# interfacez_main_r2_3.net
KiCad netlist of a schematic drawn in EAGLE
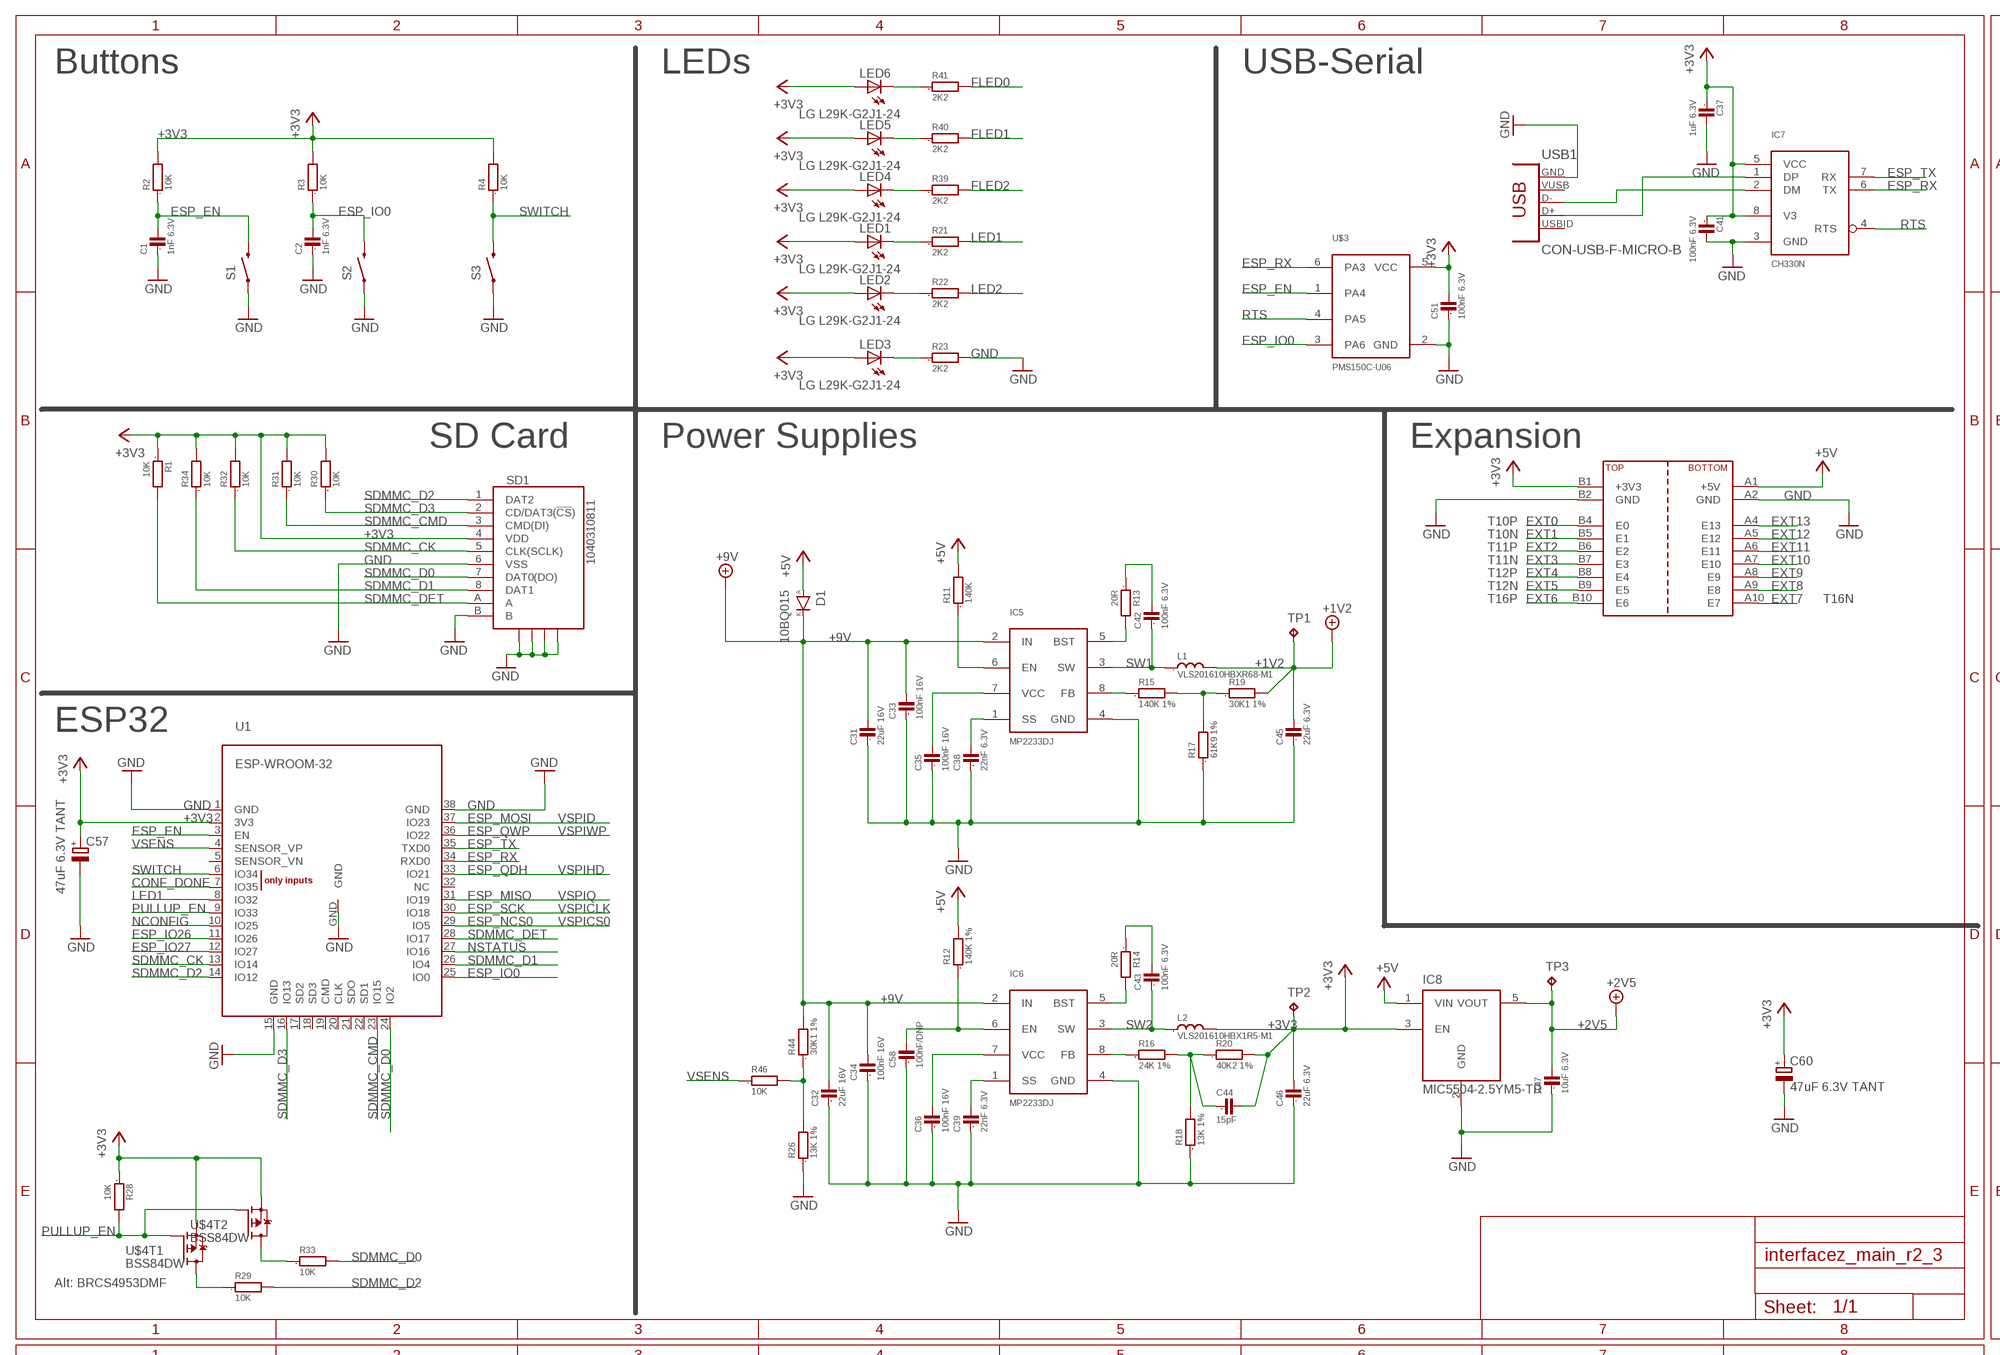
[diagram p0: schematic, sheet 1, part 1 of 3]
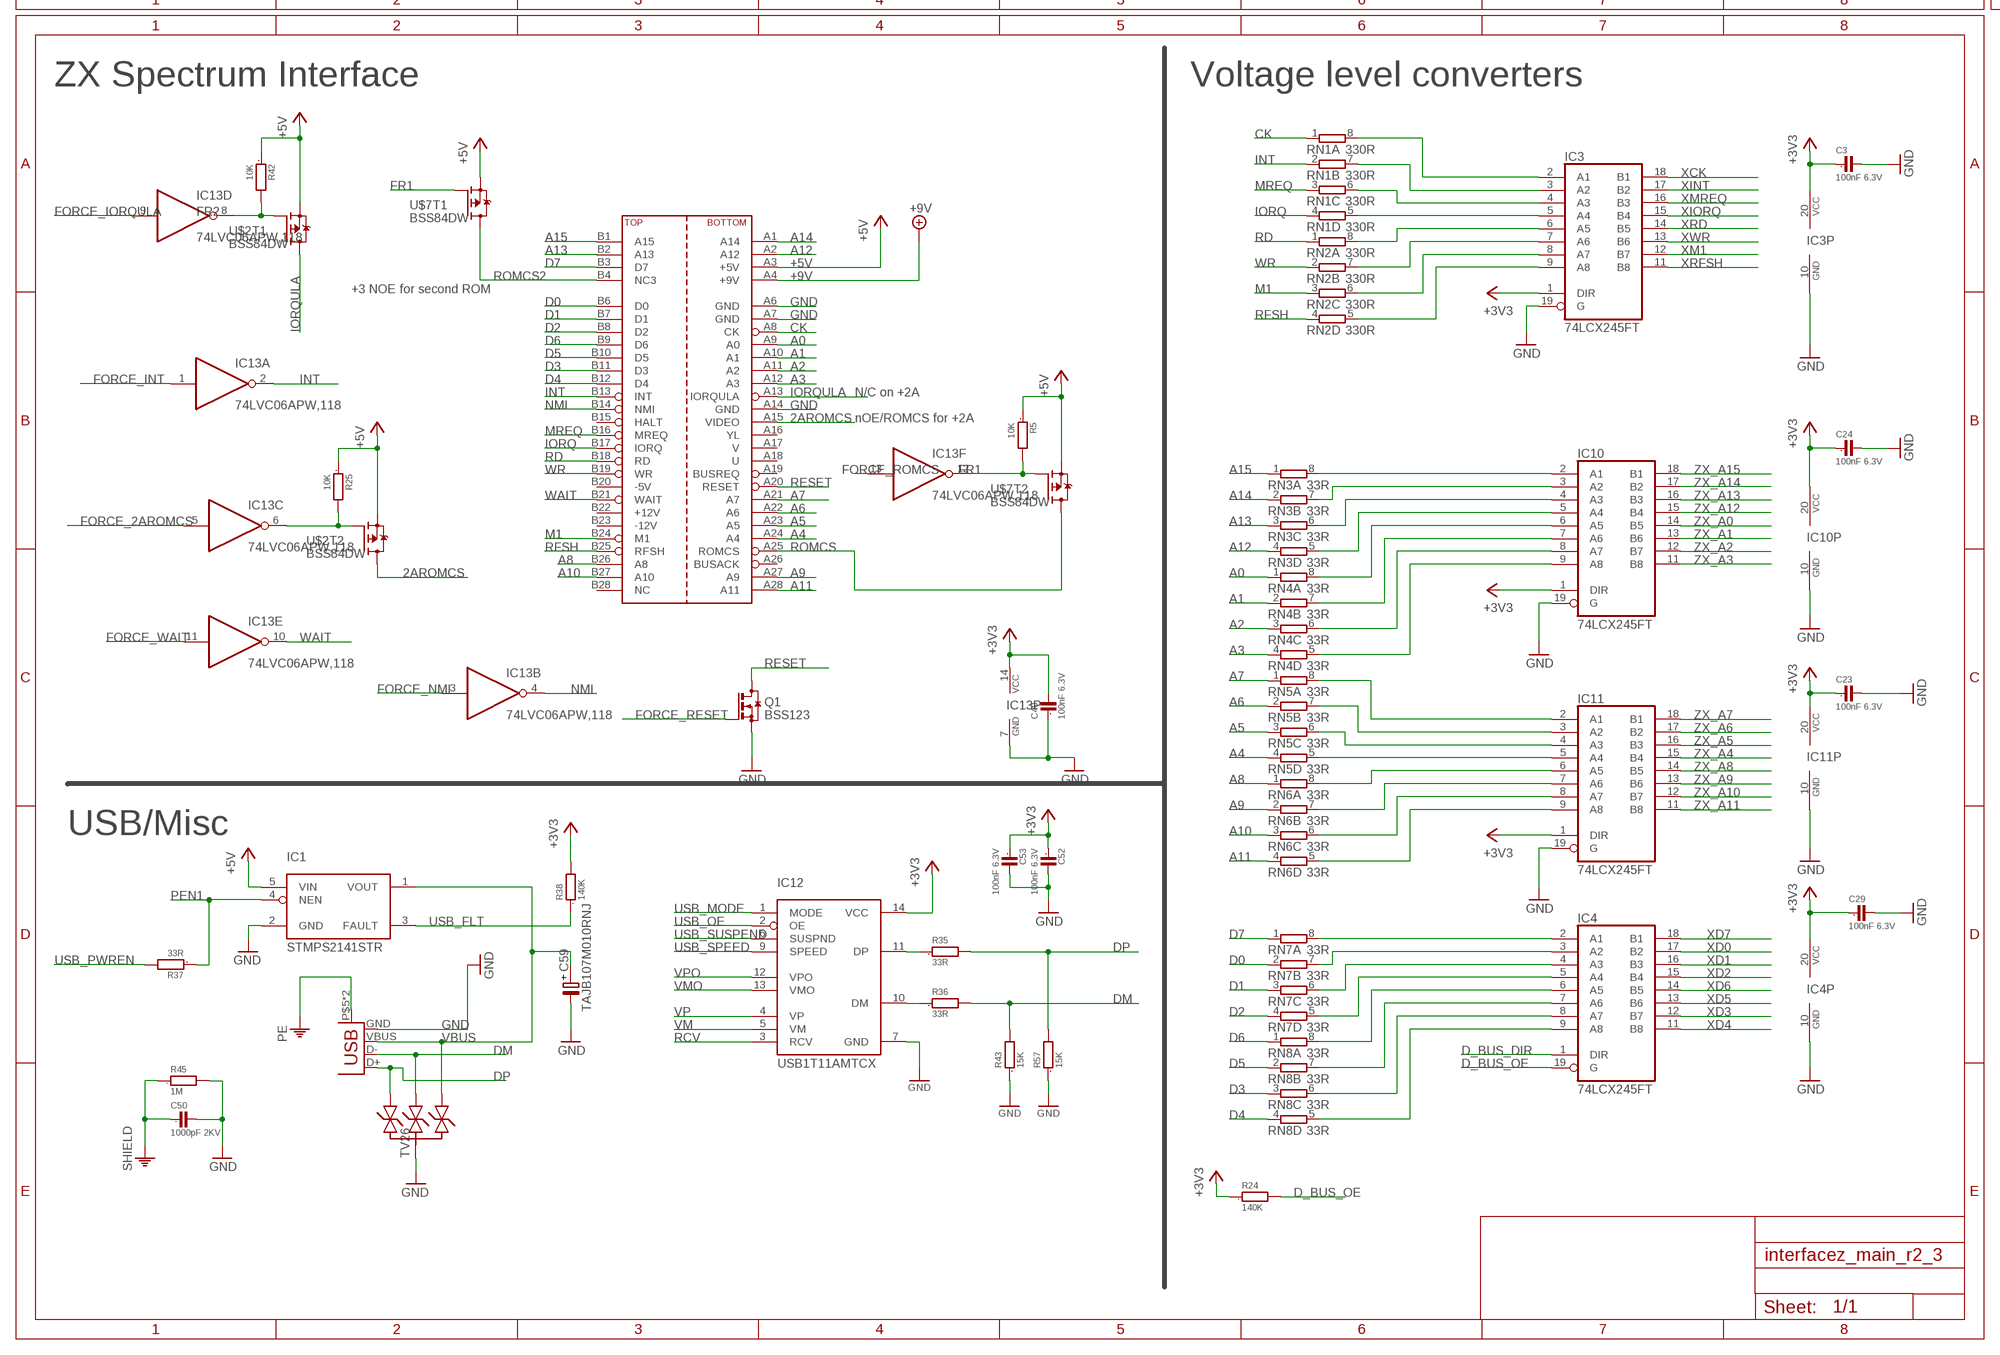
[diagram p1: schematic, sheet 1, part 2 of 3]
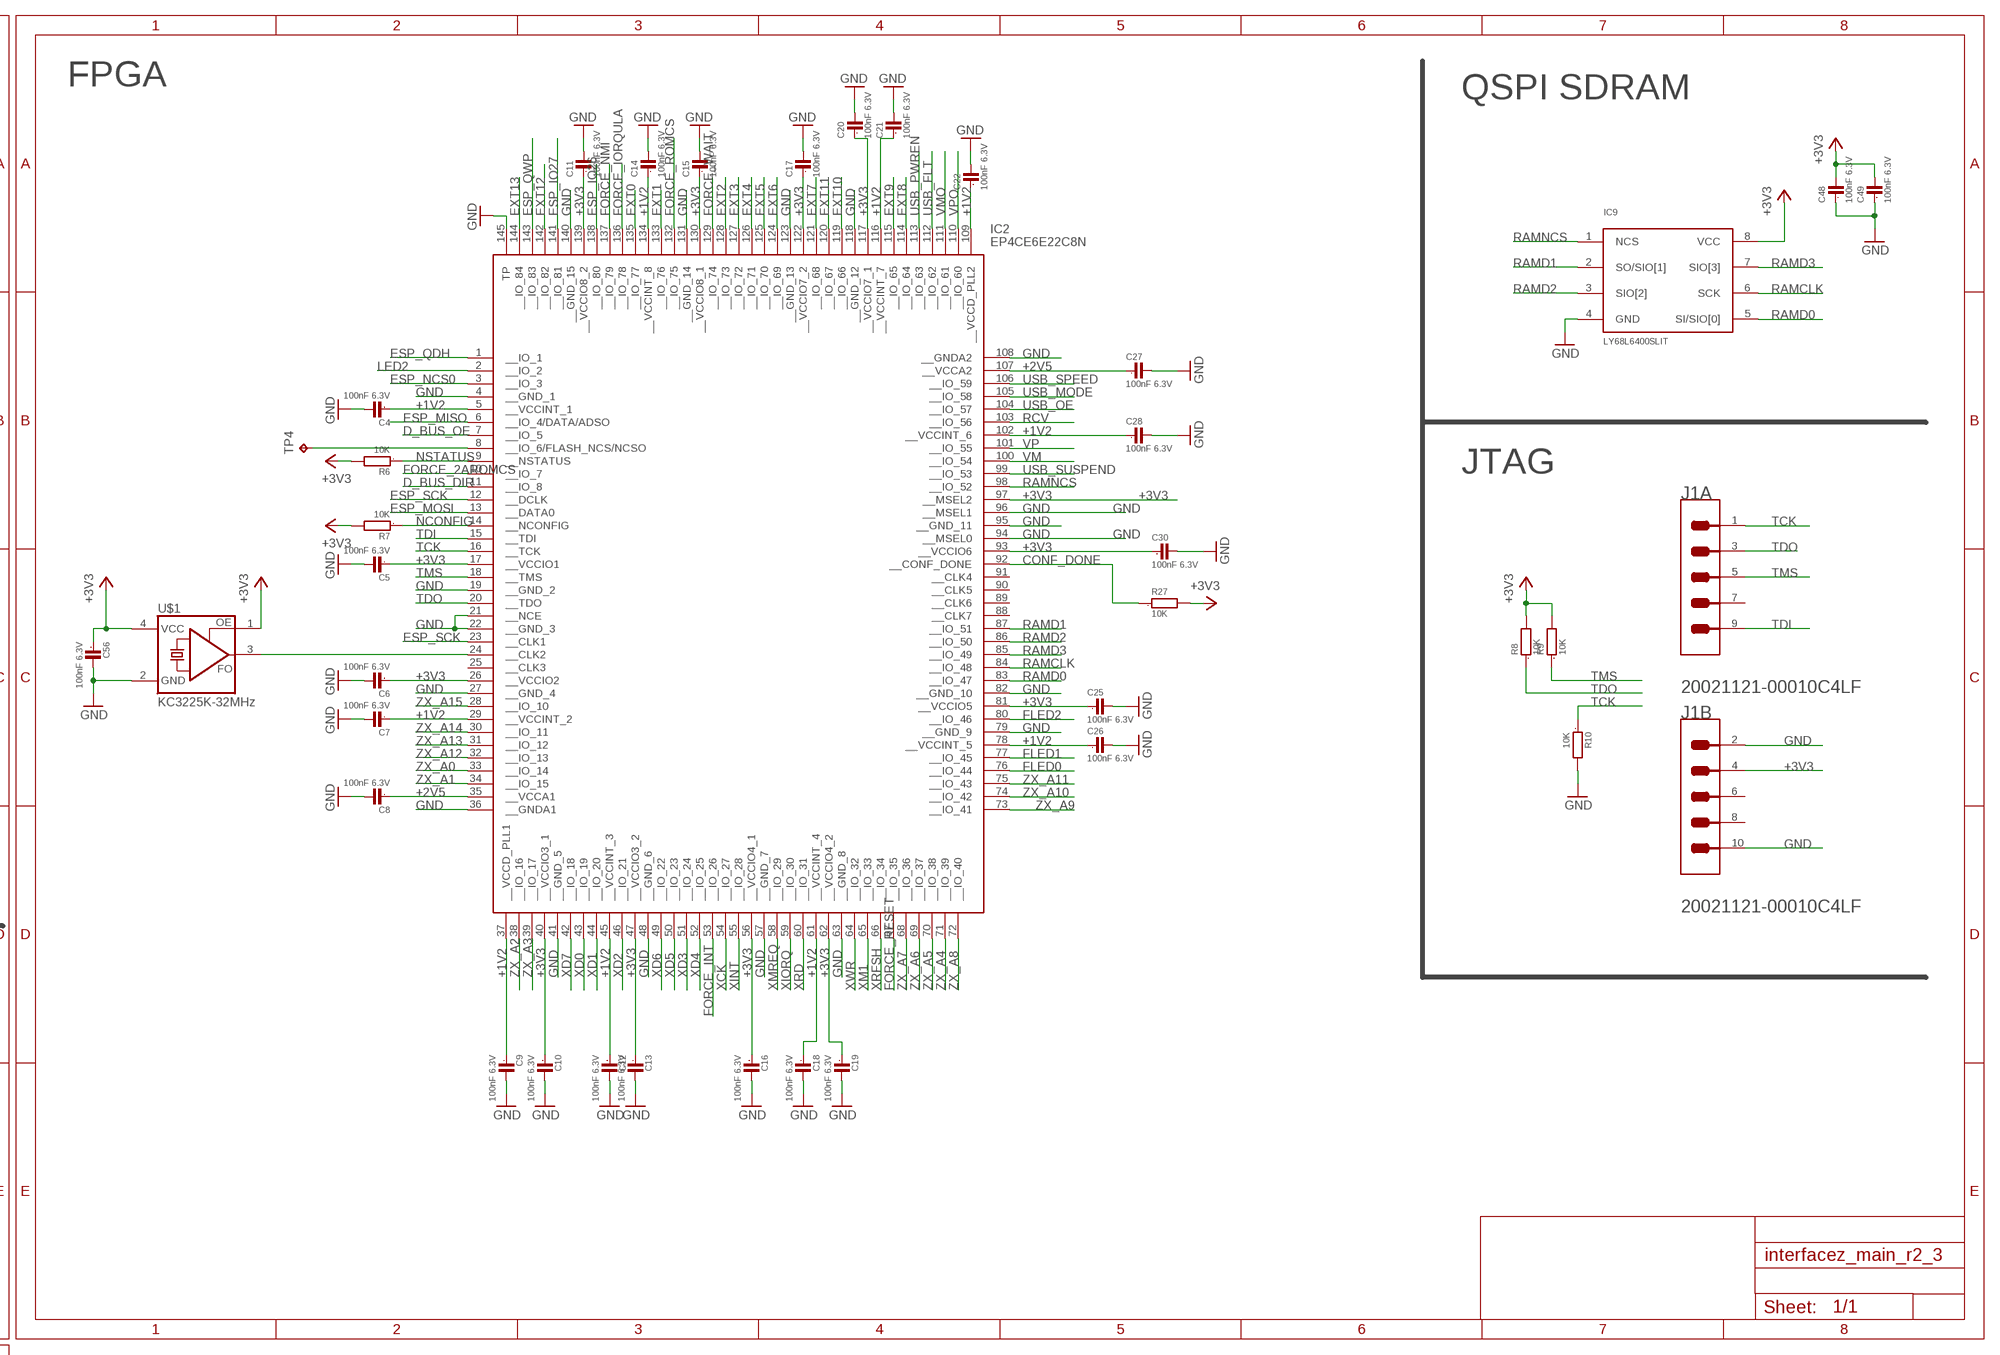
[diagram p2: schematic, sheet 1, part 3 of 3]

(export (version "E")
  (design (tool "Eeschema 10.0.6"))
  (components
    (comp (ref "C1")
      (value "1nF 6.3V")
      (footprint "eagle-import:0603")
      (libsource (lib "eagle-import") (part "C0603"))
    )
    (comp (ref "C2")
      (value "1nF 6.3V")
      (footprint "eagle-import:0603")
      (libsource (lib "eagle-import") (part "C0603"))
    )
    (comp (ref "C3")
      (value "100nF 6.3V")
      (footprint "eagle-import:0603")
      (libsource (lib "eagle-import") (part "C0603"))
    )
    (comp (ref "C4")
      (value "100nF 6.3V")
      (footprint "eagle-import:0603")
      (libsource (lib "eagle-import") (part "C0603"))
    )
    (comp (ref "C5")
      (value "100nF 6.3V")
      (footprint "eagle-import:0603")
      (libsource (lib "eagle-import") (part "C0603"))
    )
    (comp (ref "C6")
      (value "100nF 6.3V")
      (footprint "eagle-import:0603")
      (libsource (lib "eagle-import") (part "C0603"))
    )
    (comp (ref "C7")
      (value "100nF 6.3V")
      (footprint "eagle-import:0603")
      (libsource (lib "eagle-import") (part "C0603"))
    )
    (comp (ref "C8")
      (value "100nF 6.3V")
      (footprint "eagle-import:0603")
      (libsource (lib "eagle-import") (part "C0603"))
    )
    (comp (ref "C9")
      (value "100nF 6.3V")
      (footprint "eagle-import:0603")
      (libsource (lib "eagle-import") (part "C0603"))
    )
    (comp (ref "C10")
      (value "100nF 6.3V")
      (footprint "eagle-import:0603")
      (libsource (lib "eagle-import") (part "C0603"))
    )
    (comp (ref "C11")
      (value "100nF 6.3V")
      (footprint "eagle-import:0603")
      (libsource (lib "eagle-import") (part "C0603"))
    )
    (comp (ref "C12")
      (value "100nF 6.3V")
      (footprint "eagle-import:0603")
      (libsource (lib "eagle-import") (part "C0603"))
    )
    (comp (ref "C13")
      (value "100nF 6.3V")
      (footprint "eagle-import:0603")
      (libsource (lib "eagle-import") (part "C0603"))
    )
    (comp (ref "C14")
      (value "100nF 6.3V")
      (footprint "eagle-import:0603")
      (libsource (lib "eagle-import") (part "C0603"))
    )
    (comp (ref "C15")
      (value "100nF 6.3V")
      (footprint "eagle-import:0603")
      (libsource (lib "eagle-import") (part "C0603"))
    )
    (comp (ref "C16")
      (value "100nF 6.3V")
      (footprint "eagle-import:0603")
      (libsource (lib "eagle-import") (part "C0603"))
    )
    (comp (ref "C17")
      (value "100nF 6.3V")
      (footprint "eagle-import:0603")
      (libsource (lib "eagle-import") (part "C0603"))
    )
    (comp (ref "C18")
      (value "100nF 6.3V")
      (footprint "eagle-import:0603")
      (libsource (lib "eagle-import") (part "C0603"))
    )
    (comp (ref "C19")
      (value "100nF 6.3V")
      (footprint "eagle-import:0603")
      (libsource (lib "eagle-import") (part "C0603"))
    )
    (comp (ref "C20")
      (value "100nF 6.3V")
      (footprint "eagle-import:0603")
      (libsource (lib "eagle-import") (part "C0603"))
    )
    (comp (ref "C21")
      (value "100nF 6.3V")
      (footprint "eagle-import:0603")
      (libsource (lib "eagle-import") (part "C0603"))
    )
    (comp (ref "C22")
      (value "100nF 6.3V")
      (footprint "eagle-import:0603")
      (libsource (lib "eagle-import") (part "C0603"))
    )
    (comp (ref "C23")
      (value "100nF 6.3V")
      (footprint "eagle-import:0603")
      (libsource (lib "eagle-import") (part "C0603"))
    )
    (comp (ref "C24")
      (value "100nF 6.3V")
      (footprint "eagle-import:0603")
      (libsource (lib "eagle-import") (part "C0603"))
    )
    (comp (ref "C25")
      (value "100nF 6.3V")
      (footprint "eagle-import:0603")
      (libsource (lib "eagle-import") (part "C0603"))
    )
    (comp (ref "C26")
      (value "100nF 6.3V")
      (footprint "eagle-import:0603")
      (libsource (lib "eagle-import") (part "C0603"))
    )
    (comp (ref "C27")
      (value "100nF 6.3V")
      (footprint "eagle-import:0603")
      (libsource (lib "eagle-import") (part "C0603"))
    )
    (comp (ref "C28")
      (value "100nF 6.3V")
      (footprint "eagle-import:0603")
      (libsource (lib "eagle-import") (part "C0603"))
    )
    (comp (ref "C29")
      (value "100nF 6.3V")
      (footprint "eagle-import:0603")
      (libsource (lib "eagle-import") (part "C0603"))
    )
    (comp (ref "C30")
      (value "100nF 6.3V")
      (footprint "eagle-import:0603")
      (libsource (lib "eagle-import") (part "C0603"))
    )
    (comp (ref "C31")
      (value "22uF 16V")
      (footprint "eagle-import:1210")
      (libsource (lib "eagle-import") (part "C1210"))
    )
    (comp (ref "C32")
      (value "22uF 16V")
      (footprint "eagle-import:1210")
      (libsource (lib "eagle-import") (part "C1210"))
    )
    (comp (ref "C33")
      (value "100nF 16V")
      (footprint "eagle-import:0603")
      (libsource (lib "eagle-import") (part "C0603"))
    )
    (comp (ref "C34")
      (value "100nF 16V")
      (footprint "eagle-import:0603")
      (libsource (lib "eagle-import") (part "C0603"))
    )
    (comp (ref "C35")
      (value "100nF 16V")
      (footprint "eagle-import:0603")
      (libsource (lib "eagle-import") (part "C0603"))
    )
    (comp (ref "C36")
      (value "100nF 16V")
      (footprint "eagle-import:0603")
      (libsource (lib "eagle-import") (part "C0603"))
    )
    (comp (ref "C37")
      (value "1uF 6.3V")
      (footprint "eagle-import:0603")
      (libsource (lib "eagle-import") (part "C0603"))
    )
    (comp (ref "C38")
      (value "22nF 6.3V")
      (footprint "eagle-import:0603")
      (libsource (lib "eagle-import") (part "C0603"))
    )
    (comp (ref "C39")
      (value "22nF 6.3V")
      (footprint "eagle-import:0603")
      (libsource (lib "eagle-import") (part "C0603"))
    )
    (comp (ref "C40")
      (value "100nF 6.3V")
      (footprint "eagle-import:0603")
      (libsource (lib "eagle-import") (part "C0603"))
    )
    (comp (ref "C41")
      (value "100nF 6.3V")
      (footprint "eagle-import:0603")
      (libsource (lib "eagle-import") (part "C0603"))
    )
    (comp (ref "C42")
      (value "100nF 6.3V")
      (footprint "eagle-import:0603")
      (libsource (lib "eagle-import") (part "C0603"))
    )
    (comp (ref "C43")
      (value "100nF 6.3V")
      (footprint "eagle-import:0603")
      (libsource (lib "eagle-import") (part "C0603"))
    )
    (comp (ref "C44")
      (value "15pF")
      (footprint "eagle-import:0603")
      (libsource (lib "eagle-import") (part "C0603"))
    )
    (comp (ref "C45")
      (value "22uF 6.3V")
      (footprint "eagle-import:0805")
      (libsource (lib "eagle-import") (part "C0805"))
    )
    (comp (ref "C46")
      (value "22uF 6.3V")
      (footprint "eagle-import:0805")
      (libsource (lib "eagle-import") (part "C0805"))
    )
    (comp (ref "C47")
      (value "10uF 6.3V")
      (footprint "eagle-import:0805")
      (libsource (lib "eagle-import") (part "C0805"))
    )
    (comp (ref "C48")
      (value "100nF 6.3V")
      (footprint "eagle-import:0603")
      (libsource (lib "eagle-import") (part "C0603"))
    )
    (comp (ref "C49")
      (value "100nF 6.3V")
      (footprint "eagle-import:0603")
      (libsource (lib "eagle-import") (part "C0603"))
    )
    (comp (ref "C50")
      (value "1000pF 2KV")
      (footprint "eagle-import:1210")
      (libsource (lib "eagle-import") (part "C1210"))
    )
    (comp (ref "C51")
      (value "100nF 6.3V")
      (footprint "eagle-import:0603")
      (libsource (lib "eagle-import") (part "C0603"))
    )
    (comp (ref "C52")
      (value "100nF 6.3V")
      (footprint "eagle-import:0603")
      (libsource (lib "eagle-import") (part "C0603"))
    )
    (comp (ref "C53")
      (value "100nF 6.3V")
      (footprint "eagle-import:0603")
      (libsource (lib "eagle-import") (part "C0603"))
    )
    (comp (ref "C56")
      (value "100nF 6.3V")
      (footprint "eagle-import:0603")
      (libsource (lib "eagle-import") (part "C0603"))
    )
    (comp (ref "C57")
      (value "47uF 6.3V TANT")
      (footprint "eagle-import:TANT_CASE_A")
      (libsource (lib "eagle-import") (part "TANT_CASE_A"))
    )
    (comp (ref "C58")
      (value "100nF/DNP")
      (footprint "eagle-import:0603")
      (libsource (lib "eagle-import") (part "C0603"))
    )
    (comp (ref "C59")
      (value "TAJB107M010RNJ")
      (footprint "eagle-import:TE-B-3528")
      (libsource (lib "eagle-import") (part "C-PR-SMD-TE-B"))
    )
    (comp (ref "C60")
      (value "47uF 6.3V TANT")
      (footprint "eagle-import:TANT_CASE_A")
      (libsource (lib "eagle-import") (part "TANT_CASE_A"))
    )
    (comp (ref "CONN1")
      (value "ZX_EDGE_DAUGHTERBOARD")
      (footprint "eagle-import:ZX-EDGE-DAUGHTERBOARD")
      (libsource (lib "eagle-import") (part "ZX_EDGE_DAUGHTERBOARD"))
    )
    (comp (ref "D1")
      (value "10BQ015")
      (footprint "eagle-import:SMB")
      (libsource (lib "eagle-import") (part "DIODE-SCHOTTKY_SMB"))
    )
    (comp (ref "IC1")
      (value "STMPS2141STR")
      (footprint "eagle-import:SOT23-5L")
      (libsource (lib "eagle-import") (part "STMPS2141STR"))
    )
    (comp (ref "IC2")
      (value "EP4CE6E22C8N")
      (footprint "eagle-import:QFP50P2200X2200X165-145N")
      (fields (field (name "MOUSER_PART_NUMBER") "989-EP4CE6E22C8N"))
      (libsource (lib "eagle-import") (part "EP4CE6E22C8N"))
    )
    (comp (ref "IC3")
      (value "74LCX245FT")
      (footprint "eagle-import:TSSOP20")
      (libsource (lib "eagle-import") (part "74245"))
    )
    (comp (ref "IC4")
      (value "74LCX245FT")
      (footprint "eagle-import:TSSOP20")
      (libsource (lib "eagle-import") (part "74245"))
    )
    (comp (ref "IC5")
      (value "MP2233DJ")
      (footprint "eagle-import:SOT23-8L")
      (libsource (lib "eagle-import") (part "MP2233DJ"))
    )
    (comp (ref "IC6")
      (value "MP2233DJ")
      (footprint "eagle-import:SOT23-8L")
      (libsource (lib "eagle-import") (part "MP2233DJ"))
    )
    (comp (ref "IC7")
      (value "CH330N")
      (footprint "eagle-import:SOIC8")
      (libsource (lib "eagle-import") (part "CH330N"))
    )
    (comp (ref "IC8")
      (value "MIC5504-2.5YM5-TR")
      (footprint "eagle-import:SOT23-5L")
      (libsource (lib "eagle-import") (part "MIC550X"))
    )
    (comp (ref "IC9")
      (value "LY68L6400SLIT")
      (footprint "eagle-import:SOIC8")
      (libsource (lib "eagle-import") (part "LY68L6400SLIT"))
    )
    (comp (ref "IC10")
      (value "74LCX245FT")
      (footprint "eagle-import:TSSOP20")
      (libsource (lib "eagle-import") (part "74245"))
    )
    (comp (ref "IC11")
      (value "74LCX245FT")
      (footprint "eagle-import:TSSOP20")
      (libsource (lib "eagle-import") (part "74245"))
    )
    (comp (ref "IC12")
      (value "USB1T11AMTCX")
      (footprint "eagle-import:TSSOP14")
      (libsource (lib "eagle-import") (part "USB1TMTCX11A"))
    )
    (comp (ref "IC13")
      (value "74LVC06APW,118")
      (footprint "eagle-import:TSSOP14")
      (libsource (lib "eagle-import") (part "7406APW,118LVC"))
    )
    (comp (ref "J1")
      (value "AMPHENOL_ICC_-_FCI_20021121-00010C4LFAMPHENOL_ICC_-_FCI_20021121-00010C4LF_0_0")
      (footprint "eagle-import:AMPHENOL_ICC_-_FCI_20021121-00010C4LF_0")
      (fields
        (field (name "DIGIKEY_PART_NUMBER") "609-3695-1-ND")
        (field (name "MF") "Amphenol ICC / FCI")
        (field (name "MOUSER_PART_NUMBER") "649-202112100010C4LF")
      )
      (libsource (lib "eagle-import") (part "AMPHENOL_ICC_-_FCI_20021121-00010C4LFAMPHENOL_ICC_-_FCI_20021121-00010C4LF_0_0"))
    )
    (comp (ref "L1")
      (value "VLS201610HBXR68-M1")
      (footprint "eagle-import:IND_0806")
      (libsource (lib "eagle-import") (part "VLS201610HBXR68-M1"))
    )
    (comp (ref "L2")
      (value "VLS201610HBX1R5-M1")
      (footprint "eagle-import:IND_0806")
      (libsource (lib "eagle-import") (part "VLS201610HBX1R5-M1"))
    )
    (comp (ref "LED1")
      (value "LG L29K-G2J1-24")
      (footprint "eagle-import:LED-603")
      (libsource (lib "eagle-import") (part "LED-0603"))
    )
    (comp (ref "LED2")
      (value "LG L29K-G2J1-24")
      (footprint "eagle-import:LED-603")
      (libsource (lib "eagle-import") (part "LED-0603"))
    )
    (comp (ref "LED3")
      (value "LG L29K-G2J1-24")
      (footprint "eagle-import:LED-603")
      (libsource (lib "eagle-import") (part "LED-0603"))
    )
    (comp (ref "LED4")
      (value "LG L29K-G2J1-24")
      (footprint "eagle-import:LED-603")
      (libsource (lib "eagle-import") (part "LED-0603"))
    )
    (comp (ref "LED5")
      (value "LG L29K-G2J1-24")
      (footprint "eagle-import:LED-603")
      (libsource (lib "eagle-import") (part "LED-0603"))
    )
    (comp (ref "LED6")
      (value "LG L29K-G2J1-24")
      (footprint "eagle-import:LED-603")
      (libsource (lib "eagle-import") (part "LED-0603"))
    )
    (comp (ref "Q1")
      (value "BSS123")
      (footprint "eagle-import:SOT23")
      (libsource (lib "eagle-import") (part "BSS123"))
    )
    (comp (ref "R1")
      (value "10K")
      (footprint "eagle-import:0603")
      (libsource (lib "eagle-import") (part "R0603"))
    )
    (comp (ref "R2")
      (value "10K")
      (footprint "eagle-import:0603")
      (libsource (lib "eagle-import") (part "R0603"))
    )
    (comp (ref "R3")
      (value "10K")
      (footprint "eagle-import:0603")
      (libsource (lib "eagle-import") (part "R0603"))
    )
    (comp (ref "R4")
      (value "10K")
      (footprint "eagle-import:0603")
      (libsource (lib "eagle-import") (part "R0603"))
    )
    (comp (ref "R5")
      (value "10K")
      (footprint "eagle-import:0603")
      (libsource (lib "eagle-import") (part "R0603"))
    )
    (comp (ref "R6")
      (value "10K")
      (footprint "eagle-import:0603")
      (libsource (lib "eagle-import") (part "R0603"))
    )
    (comp (ref "R7")
      (value "10K")
      (footprint "eagle-import:0603")
      (libsource (lib "eagle-import") (part "R0603"))
    )
    (comp (ref "R8")
      (value "10K")
      (footprint "eagle-import:0603")
      (libsource (lib "eagle-import") (part "R0603"))
    )
    (comp (ref "R9")
      (value "10K")
      (footprint "eagle-import:0603")
      (libsource (lib "eagle-import") (part "R0603"))
    )
    (comp (ref "R10")
      (value "10K")
      (footprint "eagle-import:0603")
      (libsource (lib "eagle-import") (part "R0603"))
    )
    (comp (ref "R11")
      (value "140K")
      (footprint "eagle-import:0603")
      (libsource (lib "eagle-import") (part "R0603"))
    )
    (comp (ref "R12")
      (value "140K 1%")
      (footprint "eagle-import:0603")
      (libsource (lib "eagle-import") (part "R0603"))
    )
    (comp (ref "R13")
      (value "20R")
      (footprint "eagle-import:0603")
      (libsource (lib "eagle-import") (part "R0603"))
    )
    (comp (ref "R14")
      (value "20R")
      (footprint "eagle-import:0603")
      (libsource (lib "eagle-import") (part "R0603"))
    )
    (comp (ref "R15")
      (value "140K 1%")
      (footprint "eagle-import:0603")
      (libsource (lib "eagle-import") (part "R0603"))
    )
    (comp (ref "R16")
      (value "24K 1%")
      (footprint "eagle-import:0603")
      (libsource (lib "eagle-import") (part "R0603"))
    )
    (comp (ref "R17")
      (value "61K9 1%")
      (footprint "eagle-import:0603")
      (libsource (lib "eagle-import") (part "R0603"))
    )
    (comp (ref "R18")
      (value "13K 1%")
      (footprint "eagle-import:0603")
      (libsource (lib "eagle-import") (part "R0603"))
    )
    (comp (ref "R19")
      (value "30K1 1%")
      (footprint "eagle-import:0603")
      (libsource (lib "eagle-import") (part "R0603"))
    )
    (comp (ref "R20")
      (value "40K2 1%")
      (footprint "eagle-import:0603")
      (libsource (lib "eagle-import") (part "R0603"))
    )
    (comp (ref "R21")
      (value "2K2")
      (footprint "eagle-import:0603")
      (libsource (lib "eagle-import") (part "R0603"))
    )
    (comp (ref "R22")
      (value "2K2")
      (footprint "eagle-import:0603")
      (libsource (lib "eagle-import") (part "R0603"))
    )
    (comp (ref "R23")
      (value "2K2")
      (footprint "eagle-import:0603")
      (libsource (lib "eagle-import") (part "R0603"))
    )
    (comp (ref "R24")
      (value "140K")
      (footprint "eagle-import:0603")
      (libsource (lib "eagle-import") (part "R0603"))
    )
    (comp (ref "R25")
      (value "10K")
      (footprint "eagle-import:0603")
      (libsource (lib "eagle-import") (part "R0603"))
    )
    (comp (ref "R26")
      (value "13K 1%")
      (footprint "eagle-import:0603")
      (libsource (lib "eagle-import") (part "R0603"))
    )
    (comp (ref "R27")
      (value "10K")
      (footprint "eagle-import:0603")
      (libsource (lib "eagle-import") (part "R0603"))
    )
    (comp (ref "R28")
      (value "10K")
      (footprint "eagle-import:0603")
      (libsource (lib "eagle-import") (part "R0603"))
    )
    (comp (ref "R29")
      (value "10K")
      (footprint "eagle-import:0603")
      (libsource (lib "eagle-import") (part "R0603"))
    )
    (comp (ref "R30")
      (value "10K")
      (footprint "eagle-import:0603")
      (libsource (lib "eagle-import") (part "R0603"))
    )
    (comp (ref "R31")
      (value "10K")
      (footprint "eagle-import:0603")
      (libsource (lib "eagle-import") (part "R0603"))
    )
    (comp (ref "R32")
      (value "10K")
      (footprint "eagle-import:0603")
      (libsource (lib "eagle-import") (part "R0603"))
    )
    (comp (ref "R33")
      (value "10K")
      (footprint "eagle-import:0603")
      (libsource (lib "eagle-import") (part "R0603"))
    )
    (comp (ref "R34")
      (value "10K")
      (footprint "eagle-import:0603")
      (libsource (lib "eagle-import") (part "R0603"))
    )
    (comp (ref "R35")
      (value "33R")
      (footprint "eagle-import:0603")
      (libsource (lib "eagle-import") (part "R0603"))
    )
    (comp (ref "R36")
      (value "33R")
      (footprint "eagle-import:0603")
      (libsource (lib "eagle-import") (part "R0603"))
    )
    (comp (ref "R37")
      (value "33R")
      (footprint "eagle-import:0603")
      (libsource (lib "eagle-import") (part "R0603"))
    )
    (comp (ref "R38")
      (value "140K")
      (footprint "eagle-import:0603")
      (libsource (lib "eagle-import") (part "R0603"))
    )
    (comp (ref "R39")
      (value "2K2")
      (footprint "eagle-import:0603")
      (libsource (lib "eagle-import") (part "R0603"))
    )
    (comp (ref "R40")
      (value "2K2")
      (footprint "eagle-import:0603")
      (libsource (lib "eagle-import") (part "R0603"))
    )
    (comp (ref "R41")
      (value "2K2")
      (footprint "eagle-import:0603")
      (libsource (lib "eagle-import") (part "R0603"))
    )
    (comp (ref "R42")
      (value "10K")
      (footprint "eagle-import:0603")
      (libsource (lib "eagle-import") (part "R0603"))
    )
    (comp (ref "R43")
      (value "15K")
      (footprint "eagle-import:0603")
      (libsource (lib "eagle-import") (part "R0603"))
    )
    (comp (ref "R44")
      (value "30K1 1%")
      (footprint "eagle-import:0603")
      (libsource (lib "eagle-import") (part "R0603"))
    )
    (comp (ref "R45")
      (value "1M")
      (footprint "eagle-import:0805")
      (libsource (lib "eagle-import") (part "R0805"))
    )
    (comp (ref "R46")
      (value "10K")
      (footprint "eagle-import:0603")
      (libsource (lib "eagle-import") (part "R0603"))
    )
    (comp (ref "R57")
      (value "15K")
      (footprint "eagle-import:0603")
      (libsource (lib "eagle-import") (part "R0603"))
    )
    (comp (ref "RN1")
      (value "330R")
      (footprint "eagle-import:EXB28V")
      (libsource (lib "eagle-import") (part "4R-NEXB28V"))
    )
    (comp (ref "RN2")
      (value "330R")
      (footprint "eagle-import:EXB28V")
      (libsource (lib "eagle-import") (part "4R-NEXB28V"))
    )
    (comp (ref "RN3")
      (value "33R")
      (footprint "eagle-import:EXB28V")
      (libsource (lib "eagle-import") (part "4R-NEXB28V"))
    )
    (comp (ref "RN4")
      (value "33R")
      (footprint "eagle-import:EXB28V")
      (libsource (lib "eagle-import") (part "4R-NEXB28V"))
    )
    (comp (ref "RN5")
      (value "33R")
      (footprint "eagle-import:EXB28V")
      (libsource (lib "eagle-import") (part "4R-NEXB28V"))
    )
    (comp (ref "RN6")
      (value "33R")
      (footprint "eagle-import:EXB28V")
      (libsource (lib "eagle-import") (part "4R-NEXB28V"))
    )
    (comp (ref "RN7")
      (value "33R")
      (footprint "eagle-import:EXB28V")
      (libsource (lib "eagle-import") (part "4R-NEXB28V"))
    )
    (comp (ref "RN8")
      (value "33R")
      (footprint "eagle-import:EXB28V")
      (libsource (lib "eagle-import") (part "4R-NEXB28V"))
    )
    (comp (ref "S1")
      (value "SWITCHES_SMD-4")
      (footprint "eagle-import:TACTILE_SWITCH_TALL")
      (libsource (lib "eagle-import") (part "SWITCHES_SMD-4"))
    )
    (comp (ref "S2")
      (value "SWITCHES_SMD-4")
      (footprint "eagle-import:TACTILE_SWITCH_TALL")
      (libsource (lib "eagle-import") (part "SWITCHES_SMD-4"))
    )
    (comp (ref "S3")
      (value "SWITCHES_SMD-4")
      (footprint "eagle-import:TACTILE_SWITCH_TALL")
      (libsource (lib "eagle-import") (part "SWITCHES_SMD-4"))
    )
    (comp (ref "SD1")
      (value "1040310811")
      (footprint "eagle-import:1040310811")
      (libsource (lib "eagle-import") (part "1040310811"))
    )
    (comp (ref "TP1")
      (value "TPTP12R")
      (footprint "eagle-import:TP12R")
      (libsource (lib "eagle-import") (part "TPTP12R"))
    )
    (comp (ref "TP2")
      (value "TPTP12R")
      (footprint "eagle-import:TP12R")
      (libsource (lib "eagle-import") (part "TPTP12R"))
    )
    (comp (ref "TP3")
      (value "TPTP12R")
      (footprint "eagle-import:TP12R")
      (libsource (lib "eagle-import") (part "TPTP12R"))
    )
    (comp (ref "TP4")
      (value "TPTP08R")
      (footprint "eagle-import:TP08R")
      (libsource (lib "eagle-import") (part "TPTP08R"))
    )
    (comp (ref "TV26")
      (value "SP0503BAHT")
      (footprint "eagle-import:SP0503")
      (libsource (lib "eagle-import") (part "SP0503BAHT"))
    )
    (comp (ref "U$1")
      (value "KC3225K-32MHz")
      (footprint "eagle-import:KC3225K")
      (libsource (lib "eagle-import") (part "KC3225K"))
    )
    (comp (ref "U$2")
      (value "BSS84DW")
      (footprint "eagle-import:SOT363_INFINEON")
      (libsource (lib "eagle-import") (part "BSS84DW"))
    )
    (comp (ref "U$3")
      (value "PMS150C-U06")
      (footprint "eagle-import:SOT23-6")
      (libsource (lib "eagle-import") (part "PMS150C-U06"))
    )
    (comp (ref "U$4")
      (value "BSS84DW")
      (footprint "eagle-import:SOT363_INFINEON")
      (libsource (lib "eagle-import") (part "BSS84DW"))
    )
    (comp (ref "U$5")
      (value "INTERFACEZ_EDGEDAUGHTER")
      (footprint "eagle-import:INTERFACEZ_EXPANSION_DAUGHTERCARD")
      (libsource (lib "eagle-import") (part "INTERFACEZ_EDGEDAUGHTER"))
    )
    (comp (ref "U$7")
      (value "BSS84DW")
      (footprint "eagle-import:SOT363_INFINEON")
      (libsource (lib "eagle-import") (part "BSS84DW"))
    )
    (comp (ref "U1")
      (value "ESP-WROOM-32")
      (footprint "eagle-import:ESP-WROOM-32")
      (libsource (lib "eagle-import") (part "ESP-WROOM-32"))
    )
    (comp (ref "USB1")
      (value "CON-USB-F-MICRO-B")
      (footprint "eagle-import:CONN_USB_MICRO-B")
      (libsource (lib "eagle-import") (part "CON-USB-F-MICRO-B"))
    )
    (comp (ref "USB2")
      (value "USB-A-H")
      (footprint "eagle-import:USB-A-H")
      (libsource (lib "eagle-import") (part "USB-A-H"))
    )
  )
  (nets
    (net (code "1") (name "+1V2") (class "Default")
      (node (ref "C12") (pin "1") (pinfunction "1_1") (pintype "passive"))
      (node (ref "C14") (pin "1") (pinfunction "1_1") (pintype "passive"))
      (node (ref "C18") (pin "1") (pinfunction "1_1") (pintype "passive"))
      (node (ref "C21") (pin "1") (pinfunction "1_1") (pintype "passive"))
      (node (ref "C22") (pin "1") (pinfunction "1_1") (pintype "passive"))
      (node (ref "C26") (pin "1") (pinfunction "1_1") (pintype "passive"))
      (node (ref "C28") (pin "1") (pinfunction "1_1") (pintype "passive"))
      (node (ref "C4") (pin "1") (pinfunction "1_1") (pintype "passive"))
      (node (ref "C45") (pin "2") (pinfunction "2_2") (pintype "passive"))
      (node (ref "C7") (pin "1") (pinfunction "1_1") (pintype "passive"))
      (node (ref "C9") (pin "1") (pinfunction "1_1") (pintype "passive"))
      (node (ref "IC2") (pin "102") (pinfunction "__VCCINT_6_102") (pintype "power_in"))
      (node (ref "IC2") (pin "109") (pinfunction "__VCCD_PLL2_109") (pintype "power_in"))
      (node (ref "IC2") (pin "116") (pinfunction "__VCCINT_7_116") (pintype "power_in"))
      (node (ref "IC2") (pin "134") (pinfunction "__VCCINT_8_134") (pintype "power_in"))
      (node (ref "IC2") (pin "29") (pinfunction "__VCCINT_2_29") (pintype "power_in"))
      (node (ref "IC2") (pin "37") (pinfunction "__VCCD_PLL1_37") (pintype "power_in"))
      (node (ref "IC2") (pin "45") (pinfunction "__VCCINT_3_45") (pintype "power_in"))
      (node (ref "IC2") (pin "5") (pinfunction "__VCCINT_1_5") (pintype "power_in"))
      (node (ref "IC2") (pin "61") (pinfunction "__VCCINT_4_61") (pintype "power_in"))
      (node (ref "IC2") (pin "78") (pinfunction "__VCCINT_5_78") (pintype "power_in"))
      (node (ref "L1") (pin "P$2") (pinfunction "2_P$2") (pintype "passive"))
      (node (ref "R19") (pin "2") (pinfunction "2_2") (pintype "passive"))
      (node (ref "TP1") (pin "TP") (pinfunction "TP_TP") (pintype "input"))
    )
    (net (code "2") (name "+2V5") (class "Default")
      (node (ref "C27") (pin "1") (pinfunction "1_1") (pintype "passive"))
      (node (ref "C47") (pin "2") (pinfunction "2_2") (pintype "passive"))
      (node (ref "C8") (pin "1") (pinfunction "1_1") (pintype "passive"))
      (node (ref "IC2") (pin "107") (pinfunction "__VCCA2_107") (pintype "power_in"))
      (node (ref "IC2") (pin "35") (pinfunction "__VCCA1_35") (pintype "power_in"))
      (node (ref "IC8") (pin "5") (pinfunction "VOUT_5") (pintype "power_in"))
      (node (ref "TP3") (pin "TP") (pinfunction "TP_TP") (pintype "input"))
    )
    (net (code "3") (name "+3V3") (class "Default")
      (node (ref "C10") (pin "1") (pinfunction "1_1") (pintype "passive"))
      (node (ref "C11") (pin "1") (pinfunction "1_1") (pintype "passive"))
      (node (ref "C13") (pin "1") (pinfunction "1_1") (pintype "passive"))
      (node (ref "C15") (pin "1") (pinfunction "1_1") (pintype "passive"))
      (node (ref "C16") (pin "1") (pinfunction "1_1") (pintype "passive"))
      (node (ref "C17") (pin "1") (pinfunction "1_1") (pintype "passive"))
      (node (ref "C19") (pin "1") (pinfunction "1_1") (pintype "passive"))
      (node (ref "C20") (pin "1") (pinfunction "1_1") (pintype "passive"))
      (node (ref "C23") (pin "1") (pinfunction "1_1") (pintype "passive"))
      (node (ref "C24") (pin "1") (pinfunction "1_1") (pintype "passive"))
      (node (ref "C25") (pin "1") (pinfunction "1_1") (pintype "passive"))
      (node (ref "C29") (pin "1") (pinfunction "1_1") (pintype "passive"))
      (node (ref "C3") (pin "1") (pinfunction "1_1") (pintype "passive"))
      (node (ref "C30") (pin "1") (pinfunction "1_1") (pintype "passive"))
      (node (ref "C37") (pin "1") (pinfunction "1_1") (pintype "passive"))
      (node (ref "C40") (pin "2") (pinfunction "2_2") (pintype "passive"))
      (node (ref "C41") (pin "1") (pinfunction "1_1") (pintype "passive"))
      (node (ref "C44") (pin "2") (pinfunction "2_2") (pintype "passive"))
      (node (ref "C46") (pin "2") (pinfunction "2_2") (pintype "passive"))
      (node (ref "C48") (pin "2") (pinfunction "2_2") (pintype "passive"))
      (node (ref "C49") (pin "2") (pinfunction "2_2") (pintype "passive"))
      (node (ref "C5") (pin "1") (pinfunction "1_1") (pintype "passive"))
      (node (ref "C51") (pin "2") (pinfunction "2_2") (pintype "passive"))
      (node (ref "C52") (pin "1") (pinfunction "1_1") (pintype "passive"))
      (node (ref "C53") (pin "1") (pinfunction "1_1") (pintype "passive"))
      (node (ref "C56") (pin "1") (pinfunction "1_1") (pintype "passive"))
      (node (ref "C57") (pin "PLUS") (pinfunction "+_PLUS") (pintype "passive"))
      (node (ref "C6") (pin "1") (pinfunction "1_1") (pintype "passive"))
      (node (ref "C60") (pin "PLUS") (pinfunction "+_PLUS") (pintype "passive"))
      (node (ref "IC10") (pin "1") (pinfunction "DIR_1") (pintype "input"))
      (node (ref "IC10") (pin "20") (pinfunction "VCC_20") (pintype "power_in"))
      (node (ref "IC11") (pin "1") (pinfunction "DIR_1") (pintype "input"))
      (node (ref "IC11") (pin "20") (pinfunction "VCC_20") (pintype "power_in"))
      (node (ref "IC12") (pin "14") (pinfunction "VCC_14") (pintype "power_in"))
      (node (ref "IC13") (pin "14") (pinfunction "VCC_14") (pintype "power_in"))
      (node (ref "IC2") (pin "117") (pinfunction "__VCCIO7_1_117") (pintype "power_in"))
      (node (ref "IC2") (pin "122") (pinfunction "__VCCIO7_2_122") (pintype "power_in"))
      (node (ref "IC2") (pin "130") (pinfunction "__VCCIO8_1_130") (pintype "power_in"))
      (node (ref "IC2") (pin "139") (pinfunction "__VCCIO8_2_139") (pintype "power_in"))
      (node (ref "IC2") (pin "17") (pinfunction "__VCCIO1_17") (pintype "power_in"))
      (node (ref "IC2") (pin "26") (pinfunction "__VCCIO2_26") (pintype "power_in"))
      (node (ref "IC2") (pin "40") (pinfunction "__VCCIO3_1_40") (pintype "power_in"))
      (node (ref "IC2") (pin "47") (pinfunction "__VCCIO3_2_47") (pintype "power_in"))
      (node (ref "IC2") (pin "56") (pinfunction "__VCCIO4_1_56") (pintype "power_in"))
      (node (ref "IC2") (pin "62") (pinfunction "__VCCIO4_2_62") (pintype "power_in"))
      (node (ref "IC2") (pin "81") (pinfunction "__VCCIO5_81") (pintype "power_in"))
      (node (ref "IC2") (pin "93") (pinfunction "__VCCIO6_93") (pintype "power_in"))
      (node (ref "IC2") (pin "97") (pinfunction "__MSEL2_97") (pintype "bidirectional"))
      (node (ref "IC3") (pin "1") (pinfunction "DIR_1") (pintype "input"))
      (node (ref "IC3") (pin "20") (pinfunction "VCC_20") (pintype "power_in"))
      (node (ref "IC4") (pin "20") (pinfunction "VCC_20") (pintype "power_in"))
      (node (ref "IC7") (pin "5") (pinfunction "VCC_5") (pintype "power_in"))
      (node (ref "IC7") (pin "8") (pinfunction "V3_8") (pintype "passive"))
      (node (ref "IC8") (pin "3") (pinfunction "EN_3") (pintype "input"))
      (node (ref "IC9") (pin "8") (pinfunction "VCC_8") (pintype "power_in"))
      (node (ref "J1") (pin "4") (pinfunction "4_4") (pintype "passive"))
      (node (ref "L2") (pin "P$2") (pinfunction "2_P$2") (pintype "passive"))
      (node (ref "LED1") (pin "A") (pinfunction "A_A") (pintype "passive"))
      (node (ref "LED2") (pin "A") (pinfunction "A_A") (pintype "passive"))
      (node (ref "LED3") (pin "A") (pinfunction "A_A") (pintype "passive"))
      (node (ref "LED4") (pin "A") (pinfunction "A_A") (pintype "passive"))
      (node (ref "LED5") (pin "A") (pinfunction "A_A") (pintype "passive"))
      (node (ref "LED6") (pin "A") (pinfunction "A_A") (pintype "passive"))
      (node (ref "R1") (pin "1") (pinfunction "1_1") (pintype "passive"))
      (node (ref "R2") (pin "2") (pinfunction "2_2") (pintype "passive"))
      (node (ref "R20") (pin "2") (pinfunction "2_2") (pintype "passive"))
      (node (ref "R24") (pin "1") (pinfunction "1_1") (pintype "passive"))
      (node (ref "R27") (pin "2") (pinfunction "2_2") (pintype "passive"))
      (node (ref "R28") (pin "1") (pinfunction "1_1") (pintype "passive"))
      (node (ref "R3") (pin "2") (pinfunction "2_2") (pintype "passive"))
      (node (ref "R30") (pin "2") (pinfunction "2_2") (pintype "passive"))
      (node (ref "R31") (pin "2") (pinfunction "2_2") (pintype "passive"))
      (node (ref "R32") (pin "2") (pinfunction "2_2") (pintype "passive"))
      (node (ref "R34") (pin "2") (pinfunction "2_2") (pintype "passive"))
      (node (ref "R38") (pin "2") (pinfunction "2_2") (pintype "passive"))
      (node (ref "R4") (pin "2") (pinfunction "2_2") (pintype "passive"))
      (node (ref "R6") (pin "2") (pinfunction "2_2") (pintype "passive"))
      (node (ref "R7") (pin "2") (pinfunction "2_2") (pintype "passive"))
      (node (ref "R8") (pin "2") (pinfunction "2_2") (pintype "passive"))
      (node (ref "R9") (pin "2") (pinfunction "2_2") (pintype "passive"))
      (node (ref "SD1") (pin "4") (pinfunction "VDD_4") (pintype "power_in"))
      (node (ref "TP2") (pin "TP") (pinfunction "TP_TP") (pintype "input"))
      (node (ref "U$1") (pin "1") (pinfunction "OE_1") (pintype "input"))
      (node (ref "U$1") (pin "4") (pinfunction "VCC_4") (pintype "power_in"))
      (node (ref "U$3") (pin "5") (pinfunction "VCC_5") (pintype "power_in"))
      (node (ref "U$4") (pin "1") (pinfunction "S_1") (pintype "passive"))
      (node (ref "U$4") (pin "4") (pinfunction "S_4") (pintype "passive"))
      (node (ref "U$5") (pin "B1") (pinfunction "+3V3_B1") (pintype "power_in"))
      (node (ref "U1") (pin "2") (pinfunction "3V3_2") (pintype "bidirectional"))
    )
    (net (code "4") (name "+5V") (class "Default")
      (node (ref "CONN1") (pin "A3") (pinfunction "+5V_A3") (pintype "power_in"))
      (node (ref "D1") (pin "A") (pinfunction "A_A") (pintype "passive"))
      (node (ref "IC1") (pin "5") (pinfunction "VIN_5") (pintype "power_in"))
      (node (ref "IC8") (pin "1") (pinfunction "VIN_1") (pintype "power_in"))
      (node (ref "R11") (pin "2") (pinfunction "2_2") (pintype "passive"))
      (node (ref "R12") (pin "2") (pinfunction "2_2") (pintype "passive"))
      (node (ref "R25") (pin "1") (pinfunction "1_1") (pintype "passive"))
      (node (ref "R42") (pin "1") (pinfunction "1_1") (pintype "passive"))
      (node (ref "R5") (pin "1") (pinfunction "1_1") (pintype "passive"))
      (node (ref "U$2") (pin "1") (pinfunction "S_1") (pintype "passive"))
      (node (ref "U$2") (pin "4") (pinfunction "S_4") (pintype "passive"))
      (node (ref "U$5") (pin "A1") (pinfunction "+5V_A1") (pintype "power_in"))
      (node (ref "U$7") (pin "1") (pinfunction "S_1") (pintype "passive"))
      (node (ref "U$7") (pin "4") (pinfunction "S_4") (pintype "passive"))
    )
    (net (code "5") (name "+9V") (class "Default")
      (node (ref "C31") (pin "2") (pinfunction "2_2") (pintype "passive"))
      (node (ref "C32") (pin "2") (pinfunction "2_2") (pintype "passive"))
      (node (ref "C33") (pin "2") (pinfunction "2_2") (pintype "passive"))
      (node (ref "C34") (pin "2") (pinfunction "2_2") (pintype "passive"))
      (node (ref "CONN1") (pin "A4") (pinfunction "+9V_A4") (pintype "power_in"))
      (node (ref "D1") (pin "K") (pinfunction "K_K") (pintype "passive"))
      (node (ref "IC5") (pin "2") (pinfunction "IN_2") (pintype "power_in"))
      (node (ref "IC6") (pin "2") (pinfunction "IN_2") (pintype "power_in"))
      (node (ref "R44") (pin "2") (pinfunction "2_2") (pintype "passive"))
    )
    (net (code "6") (name "/+12V") (class "Default")
      (node (ref "CONN1") (pin "B22") (pinfunction "+12V_B22") (pintype "power_in"))
    )
    (net (code "7") (name "/-5V") (class "Default")
      (node (ref "CONN1") (pin "B20") (pinfunction "-5V_B20") (pintype "power_in"))
    )
    (net (code "8") (name "/-12V") (class "Default")
      (node (ref "CONN1") (pin "B23") (pinfunction "-12V_B23") (pintype "power_in"))
    )
    (net (code "9") (name "/2AROMCS") (class "Default")
      (node (ref "CONN1") (pin "A15") (pinfunction "VIDEO_A15") (pintype "bidirectional"))
      (node (ref "U$2") (pin "6") (pinfunction "D_6") (pintype "passive"))
    )
    (net (code "10") (name "/A0") (class "Default")
      (node (ref "CONN1") (pin "A9") (pinfunction "A0_A9") (pintype "bidirectional"))
      (node (ref "RN4") (pin "1") (pinfunction "1_1") (pintype "passive"))
    )
    (net (code "11") (name "/A1") (class "Default")
      (node (ref "CONN1") (pin "A10") (pinfunction "A1_A10") (pintype "bidirectional"))
      (node (ref "RN4") (pin "2") (pinfunction "1_2") (pintype "passive"))
    )
    (net (code "12") (name "/A2") (class "Default")
      (node (ref "CONN1") (pin "A11") (pinfunction "A2_A11") (pintype "bidirectional"))
      (node (ref "RN4") (pin "3") (pinfunction "1_3") (pintype "passive"))
    )
    (net (code "13") (name "/A3") (class "Default")
      (node (ref "CONN1") (pin "A12") (pinfunction "A3_A12") (pintype "bidirectional"))
      (node (ref "RN4") (pin "4") (pinfunction "1_4") (pintype "passive"))
    )
    (net (code "14") (name "/A4") (class "Default")
      (node (ref "CONN1") (pin "A24") (pinfunction "A4_A24") (pintype "bidirectional"))
      (node (ref "RN5") (pin "4") (pinfunction "1_4") (pintype "passive"))
    )
    (net (code "15") (name "/A5") (class "Default")
      (node (ref "CONN1") (pin "A23") (pinfunction "A5_A23") (pintype "bidirectional"))
      (node (ref "RN5") (pin "3") (pinfunction "1_3") (pintype "passive"))
    )
    (net (code "16") (name "/A6") (class "Default")
      (node (ref "CONN1") (pin "A22") (pinfunction "A6_A22") (pintype "bidirectional"))
      (node (ref "RN5") (pin "2") (pinfunction "1_2") (pintype "passive"))
    )
    (net (code "17") (name "/A7") (class "Default")
      (node (ref "CONN1") (pin "A21") (pinfunction "A7_A21") (pintype "bidirectional"))
      (node (ref "RN5") (pin "1") (pinfunction "1_1") (pintype "passive"))
    )
    (net (code "18") (name "/A8") (class "Default")
      (node (ref "CONN1") (pin "B26") (pinfunction "A8_B26") (pintype "bidirectional"))
      (node (ref "RN6") (pin "1") (pinfunction "1_1") (pintype "passive"))
    )
    (net (code "19") (name "/A9") (class "Default")
      (node (ref "CONN1") (pin "A27") (pinfunction "A9_A27") (pintype "bidirectional"))
      (node (ref "RN6") (pin "2") (pinfunction "1_2") (pintype "passive"))
    )
    (net (code "20") (name "/A10") (class "Default")
      (node (ref "CONN1") (pin "B27") (pinfunction "A10_B27") (pintype "bidirectional"))
      (node (ref "RN6") (pin "3") (pinfunction "1_3") (pintype "passive"))
    )
    (net (code "21") (name "/A11") (class "Default")
      (node (ref "CONN1") (pin "A28") (pinfunction "A11_A28") (pintype "bidirectional"))
      (node (ref "RN6") (pin "4") (pinfunction "1_4") (pintype "passive"))
    )
    (net (code "22") (name "/A12") (class "Default")
      (node (ref "CONN1") (pin "A2") (pinfunction "A12_A2") (pintype "bidirectional"))
      (node (ref "RN3") (pin "4") (pinfunction "1_4") (pintype "passive"))
    )
    (net (code "23") (name "/A13") (class "Default")
      (node (ref "CONN1") (pin "B2") (pinfunction "A13_B2") (pintype "bidirectional"))
      (node (ref "RN3") (pin "3") (pinfunction "1_3") (pintype "passive"))
    )
    (net (code "24") (name "/A14") (class "Default")
      (node (ref "CONN1") (pin "A1") (pinfunction "A14_A1") (pintype "bidirectional"))
      (node (ref "RN3") (pin "2") (pinfunction "1_2") (pintype "passive"))
    )
    (net (code "25") (name "/A15") (class "Default")
      (node (ref "CONN1") (pin "B1") (pinfunction "A15_B1") (pintype "bidirectional"))
      (node (ref "RN3") (pin "1") (pinfunction "1_1") (pintype "passive"))
    )
    (net (code "26") (name "/CK") (class "Default")
      (node (ref "CONN1") (pin "A8") (pinfunction "CK_A8") (pintype "bidirectional"))
      (node (ref "RN1") (pin "1") (pinfunction "1_1") (pintype "passive"))
    )
    (net (code "27") (name "/CONF_DONE") (class "Default")
      (node (ref "IC2") (pin "92") (pinfunction "__CONF_DONE_92") (pintype "bidirectional"))
      (node (ref "R27") (pin "1") (pinfunction "1_1") (pintype "passive"))
      (node (ref "U1") (pin "7") (pinfunction "IO35_7") (pintype "input"))
    )
    (net (code "28") (name "/D0") (class "Default")
      (node (ref "CONN1") (pin "B6") (pinfunction "D0_B6") (pintype "bidirectional"))
      (node (ref "RN7") (pin "2") (pinfunction "1_2") (pintype "passive"))
    )
    (net (code "29") (name "/D1") (class "Default")
      (node (ref "CONN1") (pin "B7") (pinfunction "D1_B7") (pintype "bidirectional"))
      (node (ref "RN7") (pin "3") (pinfunction "1_3") (pintype "passive"))
    )
    (net (code "30") (name "/D2") (class "Default")
      (node (ref "CONN1") (pin "B8") (pinfunction "D2_B8") (pintype "bidirectional"))
      (node (ref "RN7") (pin "4") (pinfunction "1_4") (pintype "passive"))
    )
    (net (code "31") (name "/D3") (class "Default")
      (node (ref "CONN1") (pin "B11") (pinfunction "D3_B11") (pintype "bidirectional"))
      (node (ref "RN8") (pin "3") (pinfunction "1_3") (pintype "passive"))
    )
    (net (code "32") (name "/D4") (class "Default")
      (node (ref "CONN1") (pin "B12") (pinfunction "D4_B12") (pintype "bidirectional"))
      (node (ref "RN8") (pin "4") (pinfunction "1_4") (pintype "passive"))
    )
    (net (code "33") (name "/D5") (class "Default")
      (node (ref "CONN1") (pin "B10") (pinfunction "D5_B10") (pintype "bidirectional"))
      (node (ref "RN8") (pin "2") (pinfunction "1_2") (pintype "passive"))
    )
    (net (code "34") (name "/D6") (class "Default")
      (node (ref "CONN1") (pin "B9") (pinfunction "D6_B9") (pintype "bidirectional"))
      (node (ref "RN8") (pin "1") (pinfunction "1_1") (pintype "passive"))
    )
    (net (code "35") (name "/D7") (class "Default")
      (node (ref "CONN1") (pin "B3") (pinfunction "D7_B3") (pintype "bidirectional"))
      (node (ref "RN7") (pin "1") (pinfunction "1_1") (pintype "passive"))
    )
    (net (code "36") (name "/DM") (class "Default")
      (node (ref "R36") (pin "2") (pinfunction "2_2") (pintype "passive"))
      (node (ref "R43") (pin "2") (pinfunction "2_2") (pintype "passive"))
      (node (ref "TV26") (pin "3") (pinfunction "B_3") (pintype "bidirectional"))
      (node (ref "USB2") (pin "D-") (pinfunction "D-_D-") (pintype "bidirectional"))
    )
    (net (code "37") (name "/DP") (class "Default")
      (node (ref "R35") (pin "2") (pinfunction "2_2") (pintype "passive"))
      (node (ref "R57") (pin "2") (pinfunction "2_2") (pintype "passive"))
      (node (ref "TV26") (pin "2") (pinfunction "A_2") (pintype "bidirectional"))
      (node (ref "USB2") (pin "D+") (pinfunction "D+_D+") (pintype "bidirectional"))
    )
    (net (code "38") (name "/D_BUS_DIR") (class "Default")
      (node (ref "IC2") (pin "11") (pinfunction "__IO_8_11") (pintype "bidirectional"))
      (node (ref "IC4") (pin "1") (pinfunction "DIR_1") (pintype "input"))
    )
    (net (code "39") (name "/D_BUS_OE") (class "Default")
      (node (ref "IC2") (pin "7") (pinfunction "__IO_5_7") (pintype "bidirectional"))
      (node (ref "IC4") (pin "19") (pinfunction "G_19") (pintype "input"))
      (node (ref "R24") (pin "2") (pinfunction "2_2") (pintype "passive"))
    )
    (net (code "40") (name "/ESP_EN") (class "Default")
      (node (ref "C1") (pin "2") (pinfunction "2_2") (pintype "passive"))
      (node (ref "R2") (pin "1") (pinfunction "1_1") (pintype "passive"))
      (node (ref "S1") (pin "B2") (pinfunction "2_B2") (pintype "passive"))
      (node (ref "U$3") (pin "1") (pinfunction "PA4_1") (pintype "passive"))
      (node (ref "U1") (pin "3") (pinfunction "EN_3") (pintype "bidirectional"))
    )
    (net (code "41") (name "/ESP_IO0") (class "Default")
      (node (ref "C2") (pin "2") (pinfunction "2_2") (pintype "passive"))
      (node (ref "R3") (pin "1") (pinfunction "1_1") (pintype "passive"))
      (node (ref "S2") (pin "B2") (pinfunction "2_B2") (pintype "passive"))
      (node (ref "U$3") (pin "3") (pinfunction "PA6_3") (pintype "passive"))
      (node (ref "U1") (pin "25") (pinfunction "IO0_25") (pintype "bidirectional"))
    )
    (net (code "42") (name "/ESP_IO26") (class "Default")
      (node (ref "IC2") (pin "138") (pinfunction "__IO_80_138") (pintype "bidirectional"))
      (node (ref "U1") (pin "11") (pinfunction "IO26_11") (pintype "bidirectional"))
    )
    (net (code "43") (name "/ESP_IO27") (class "Default")
      (node (ref "IC2") (pin "141") (pinfunction "__IO_81_141") (pintype "bidirectional"))
      (node (ref "U1") (pin "12") (pinfunction "IO27_12") (pintype "bidirectional"))
    )
    (net (code "44") (name "/ESP_MISO") (class "Default")
      (node (ref "IC2") (pin "6") (pinfunction "__IO_4/DATA/ADSO_6") (pintype "bidirectional"))
      (node (ref "U1") (pin "31") (pinfunction "IO19_31") (pintype "bidirectional"))
    )
    (net (code "45") (name "/ESP_MOSI") (class "Default")
      (node (ref "IC2") (pin "13") (pinfunction "__DATA0_13") (pintype "bidirectional"))
      (node (ref "U1") (pin "37") (pinfunction "IO23_37") (pintype "bidirectional"))
    )
    (net (code "46") (name "/ESP_NCS0") (class "Default")
      (node (ref "IC2") (pin "3") (pinfunction "__IO_3_3") (pintype "bidirectional"))
      (node (ref "U1") (pin "29") (pinfunction "IO5_29") (pintype "bidirectional"))
    )
    (net (code "47") (name "/ESP_QDH") (class "Default")
      (node (ref "IC2") (pin "1") (pinfunction "__IO_1_1") (pintype "bidirectional"))
      (node (ref "U1") (pin "33") (pinfunction "IO21_33") (pintype "bidirectional"))
    )
    (net (code "48") (name "/ESP_QWP") (class "Default")
      (node (ref "IC2") (pin "143") (pinfunction "__IO_83_143") (pintype "bidirectional"))
      (node (ref "U1") (pin "36") (pinfunction "IO22_36") (pintype "bidirectional"))
    )
    (net (code "49") (name "/ESP_RX") (class "Default")
      (node (ref "IC7") (pin "6") (pinfunction "TX_6") (pintype "output"))
      (node (ref "U$3") (pin "6") (pinfunction "PA3_6") (pintype "passive"))
      (node (ref "U1") (pin "34") (pinfunction "RXD0_34") (pintype "bidirectional"))
    )
    (net (code "50") (name "/ESP_SCK") (class "Default")
      (node (ref "IC2") (pin "12") (pinfunction "__DCLK_12") (pintype "input"))
      (node (ref "IC2") (pin "23") (pinfunction "__CLK1_23") (pintype "input"))
      (node (ref "U1") (pin "30") (pinfunction "IO18_30") (pintype "bidirectional"))
    )
    (net (code "51") (name "/ESP_TX") (class "Default")
      (node (ref "IC7") (pin "7") (pinfunction "RX_7") (pintype "input"))
      (node (ref "U1") (pin "35") (pinfunction "TXD0_35") (pintype "bidirectional"))
    )
    (net (code "52") (name "/EXT0") (class "Default")
      (node (ref "IC2") (pin "135") (pinfunction "__IO_77_135") (pintype "bidirectional"))
      (node (ref "U$5") (pin "B4") (pinfunction "E0_B4") (pintype "bidirectional"))
    )
    (net (code "53") (name "/EXT1") (class "Default")
      (node (ref "IC2") (pin "133") (pinfunction "__IO_76_133") (pintype "bidirectional"))
      (node (ref "U$5") (pin "B5") (pinfunction "E1_B5") (pintype "bidirectional"))
    )
    (net (code "54") (name "/EXT2") (class "Default")
      (node (ref "IC2") (pin "128") (pinfunction "__IO_73_128") (pintype "bidirectional"))
      (node (ref "U$5") (pin "B6") (pinfunction "E2_B6") (pintype "bidirectional"))
    )
    (net (code "55") (name "/EXT3") (class "Default")
      (node (ref "IC2") (pin "127") (pinfunction "__IO_72_127") (pintype "bidirectional"))
      (node (ref "U$5") (pin "B7") (pinfunction "E3_B7") (pintype "bidirectional"))
    )
    (net (code "56") (name "/EXT4") (class "Default")
      (node (ref "IC2") (pin "126") (pinfunction "__IO_71_126") (pintype "bidirectional"))
      (node (ref "U$5") (pin "B8") (pinfunction "E4_B8") (pintype "bidirectional"))
    )
    (net (code "57") (name "/EXT5") (class "Default")
      (node (ref "IC2") (pin "125") (pinfunction "__IO_70_125") (pintype "bidirectional"))
      (node (ref "U$5") (pin "B9") (pinfunction "E5_B9") (pintype "bidirectional"))
    )
    (net (code "58") (name "/EXT6") (class "Default")
      (node (ref "IC2") (pin "124") (pinfunction "__IO_69_124") (pintype "bidirectional"))
      (node (ref "U$5") (pin "B10") (pinfunction "E6_B10") (pintype "bidirectional"))
    )
    (net (code "59") (name "/EXT7") (class "Default")
      (node (ref "IC2") (pin "121") (pinfunction "__IO_68_121") (pintype "bidirectional"))
      (node (ref "U$5") (pin "A10") (pinfunction "E7_A10") (pintype "bidirectional"))
    )
    (net (code "60") (name "/EXT8") (class "Default")
      (node (ref "IC2") (pin "114") (pinfunction "__IO_64_114") (pintype "bidirectional"))
      (node (ref "U$5") (pin "A9") (pinfunction "E8_A9") (pintype "bidirectional"))
    )
    (net (code "61") (name "/EXT9") (class "Default")
      (node (ref "IC2") (pin "115") (pinfunction "__IO_65_115") (pintype "bidirectional"))
      (node (ref "U$5") (pin "A8") (pinfunction "E9_A8") (pintype "bidirectional"))
    )
    (net (code "62") (name "/EXT10") (class "Default")
      (node (ref "IC2") (pin "119") (pinfunction "__IO_66_119") (pintype "bidirectional"))
      (node (ref "U$5") (pin "A7") (pinfunction "E10_A7") (pintype "bidirectional"))
    )
    (net (code "63") (name "/EXT11") (class "Default")
      (node (ref "IC2") (pin "120") (pinfunction "__IO_67_120") (pintype "bidirectional"))
      (node (ref "U$5") (pin "A6") (pinfunction "E11_A6") (pintype "bidirectional"))
    )
    (net (code "64") (name "/EXT12") (class "Default")
      (node (ref "IC2") (pin "142") (pinfunction "__IO_82_142") (pintype "bidirectional"))
      (node (ref "U$5") (pin "A5") (pinfunction "E12_A5") (pintype "bidirectional"))
    )
    (net (code "65") (name "/EXT13") (class "Default")
      (node (ref "IC2") (pin "144") (pinfunction "__IO_84_144") (pintype "bidirectional"))
      (node (ref "U$5") (pin "A4") (pinfunction "E13_A4") (pintype "bidirectional"))
    )
    (net (code "66") (name "/FLED0") (class "Default")
      (node (ref "IC2") (pin "76") (pinfunction "__IO_44_76") (pintype "bidirectional"))
      (node (ref "R41") (pin "2") (pinfunction "2_2") (pintype "passive"))
    )
    (net (code "67") (name "/FLED1") (class "Default")
      (node (ref "IC2") (pin "77") (pinfunction "__IO_45_77") (pintype "bidirectional"))
      (node (ref "R40") (pin "2") (pinfunction "2_2") (pintype "passive"))
    )
    (net (code "68") (name "/FLED2") (class "Default")
      (node (ref "IC2") (pin "80") (pinfunction "__IO_46_80") (pintype "bidirectional"))
      (node (ref "R39") (pin "2") (pinfunction "2_2") (pintype "passive"))
    )
    (net (code "69") (name "/FORCE_2AROMCS") (class "Default")
      (node (ref "IC13") (pin "5") (pinfunction "I_5") (pintype "input"))
      (node (ref "IC2") (pin "10") (pinfunction "__IO_7_10") (pintype "bidirectional"))
    )
    (net (code "70") (name "/FORCE_INT") (class "Default")
      (node (ref "IC13") (pin "1") (pinfunction "I_1") (pintype "input"))
      (node (ref "IC2") (pin "53") (pinfunction "__IO_26_53") (pintype "bidirectional"))
    )
    (net (code "71") (name "/FORCE_IORQULA") (class "Default")
      (node (ref "IC13") (pin "9") (pinfunction "I_9") (pintype "input"))
      (node (ref "IC2") (pin "136") (pinfunction "__IO_78_136") (pintype "bidirectional"))
    )
    (net (code "72") (name "/FORCE_NMI") (class "Default")
      (node (ref "IC13") (pin "3") (pinfunction "I_3") (pintype "input"))
      (node (ref "IC2") (pin "137") (pinfunction "__IO_79_137") (pintype "bidirectional"))
    )
    (net (code "73") (name "/FORCE_RESET") (class "Default")
      (node (ref "IC2") (pin "67") (pinfunction "__IO_35_67") (pintype "bidirectional"))
      (node (ref "Q1") (pin "1") (pinfunction "G_1") (pintype "passive"))
    )
    (net (code "74") (name "/FORCE_ROMCS") (class "Default")
      (node (ref "IC13") (pin "13") (pinfunction "I_13") (pintype "input"))
      (node (ref "IC2") (pin "132") (pinfunction "__IO_75_132") (pintype "bidirectional"))
    )
    (net (code "75") (name "/FORCE_WAIT") (class "Default")
      (node (ref "IC13") (pin "11") (pinfunction "I_11") (pintype "input"))
      (node (ref "IC2") (pin "129") (pinfunction "__IO_74_129") (pintype "bidirectional"))
    )
    (net (code "76") (name "/FR1") (class "Default")
      (node (ref "IC13") (pin "12") (pinfunction "O_12") (pintype "open_collector"))
      (node (ref "R5") (pin "2") (pinfunction "2_2") (pintype "passive"))
      (node (ref "U$7") (pin "2") (pinfunction "G_2") (pintype "passive"))
      (node (ref "U$7") (pin "5") (pinfunction "G_5") (pintype "passive"))
    )
    (net (code "77") (name "/FR2") (class "Default")
      (node (ref "IC13") (pin "8") (pinfunction "O_8") (pintype "open_collector"))
      (node (ref "R42") (pin "2") (pinfunction "2_2") (pintype "passive"))
      (node (ref "U$2") (pin "5") (pinfunction "G_5") (pintype "passive"))
    )
    (net (code "78") (name "/INT") (class "Default")
      (node (ref "CONN1") (pin "B13") (pinfunction "INT_B13") (pintype "bidirectional"))
      (node (ref "IC13") (pin "2") (pinfunction "O_2") (pintype "open_collector"))
      (node (ref "RN1") (pin "2") (pinfunction "1_2") (pintype "passive"))
    )
    (net (code "79") (name "/IORQ") (class "Default")
      (node (ref "CONN1") (pin "B17") (pinfunction "IORQ_B17") (pintype "bidirectional"))
      (node (ref "RN1") (pin "4") (pinfunction "1_4") (pintype "passive"))
    )
    (net (code "80") (name "/IORQULA") (class "Default")
      (node (ref "CONN1") (pin "A13") (pinfunction "IORQULA_A13") (pintype "bidirectional"))
      (node (ref "U$2") (pin "3") (pinfunction "D_3") (pintype "passive"))
    )
    (net (code "81") (name "/LED1") (class "Default")
      (node (ref "R21") (pin "2") (pinfunction "2_2") (pintype "passive"))
      (node (ref "U1") (pin "8") (pinfunction "IO32_8") (pintype "bidirectional"))
    )
    (net (code "82") (name "/LED2") (class "Default")
      (node (ref "IC2") (pin "2") (pinfunction "__IO_2_2") (pintype "bidirectional"))
      (node (ref "R22") (pin "2") (pinfunction "2_2") (pintype "passive"))
    )
    (net (code "83") (name "/M1") (class "Default")
      (node (ref "CONN1") (pin "B24") (pinfunction "M1_B24") (pintype "bidirectional"))
      (node (ref "RN2") (pin "3") (pinfunction "1_3") (pintype "passive"))
    )
    (net (code "84") (name "/MREQ") (class "Default")
      (node (ref "CONN1") (pin "B16") (pinfunction "MREQ_B16") (pintype "bidirectional"))
      (node (ref "RN1") (pin "3") (pinfunction "1_3") (pintype "passive"))
    )
    (net (code "85") (name "/NCONFIG") (class "Default")
      (node (ref "IC2") (pin "14") (pinfunction "__NCONFIG_14") (pintype "bidirectional"))
      (node (ref "R7") (pin "1") (pinfunction "1_1") (pintype "passive"))
      (node (ref "U1") (pin "10") (pinfunction "IO25_10") (pintype "bidirectional"))
    )
    (net (code "86") (name "/NMI") (class "Default")
      (node (ref "CONN1") (pin "B14") (pinfunction "NMI_B14") (pintype "bidirectional"))
      (node (ref "IC13") (pin "4") (pinfunction "O_4") (pintype "open_collector"))
    )
    (net (code "87") (name "/NSTATUS") (class "Default")
      (node (ref "IC2") (pin "9") (pinfunction "__NSTATUS_9") (pintype "bidirectional"))
      (node (ref "R6") (pin "1") (pinfunction "1_1") (pintype "passive"))
      (node (ref "U1") (pin "27") (pinfunction "IO16_27") (pintype "bidirectional"))
    )
    (net (code "88") (name "/PEN1") (class "Default")
      (node (ref "IC1") (pin "4") (pinfunction "NEN_4") (pintype "input"))
      (node (ref "R37") (pin "1") (pinfunction "1_1") (pintype "passive"))
    )
    (net (code "89") (name "/PULLUP_EN") (class "Default")
      (node (ref "R28") (pin "2") (pinfunction "2_2") (pintype "passive"))
      (node (ref "U$4") (pin "2") (pinfunction "G_2") (pintype "passive"))
      (node (ref "U$4") (pin "5") (pinfunction "G_5") (pintype "passive"))
      (node (ref "U1") (pin "9") (pinfunction "IO33_9") (pintype "bidirectional"))
    )
    (net (code "90") (name "/RAMCLK") (class "Default")
      (node (ref "IC2") (pin "84") (pinfunction "__IO_48_84") (pintype "bidirectional"))
      (node (ref "IC9") (pin "6") (pinfunction "SCK_6") (pintype "input"))
    )
    (net (code "91") (name "/RAMD0") (class "Default")
      (node (ref "IC2") (pin "83") (pinfunction "__IO_47_83") (pintype "bidirectional"))
      (node (ref "IC9") (pin "5") (pinfunction "SI/SIO[0]_5") (pintype "bidirectional"))
    )
    (net (code "92") (name "/RAMD1") (class "Default")
      (node (ref "IC2") (pin "87") (pinfunction "__IO_51_87") (pintype "bidirectional"))
      (node (ref "IC9") (pin "2") (pinfunction "SO/SIO[1]_2") (pintype "bidirectional"))
    )
    (net (code "93") (name "/RAMD2") (class "Default")
      (node (ref "IC2") (pin "86") (pinfunction "__IO_50_86") (pintype "bidirectional"))
      (node (ref "IC9") (pin "3") (pinfunction "SIO[2]_3") (pintype "bidirectional"))
    )
    (net (code "94") (name "/RAMD3") (class "Default")
      (node (ref "IC2") (pin "85") (pinfunction "__IO_49_85") (pintype "bidirectional"))
      (node (ref "IC9") (pin "7") (pinfunction "SIO[3]_7") (pintype "bidirectional"))
    )
    (net (code "95") (name "/RAMNCS") (class "Default")
      (node (ref "IC2") (pin "98") (pinfunction "__IO_52_98") (pintype "bidirectional"))
      (node (ref "IC9") (pin "1") (pinfunction "NCS_1") (pintype "input"))
    )
    (net (code "96") (name "/RCV") (class "Default")
      (node (ref "IC12") (pin "3") (pinfunction "RCV_3") (pintype "output"))
      (node (ref "IC2") (pin "103") (pinfunction "__IO_56_103") (pintype "bidirectional"))
    )
    (net (code "97") (name "/RD") (class "Default")
      (node (ref "CONN1") (pin "B18") (pinfunction "RD_B18") (pintype "bidirectional"))
      (node (ref "RN2") (pin "1") (pinfunction "1_1") (pintype "passive"))
    )
    (net (code "98") (name "/RESET") (class "Default")
      (node (ref "CONN1") (pin "A20") (pinfunction "RESET_A20") (pintype "bidirectional"))
      (node (ref "Q1") (pin "3") (pinfunction "D_3") (pintype "passive"))
    )
    (net (code "99") (name "/RFSH") (class "Default")
      (node (ref "CONN1") (pin "B25") (pinfunction "RFSH_B25") (pintype "bidirectional"))
      (node (ref "RN2") (pin "4") (pinfunction "1_4") (pintype "passive"))
    )
    (net (code "100") (name "/ROMCS") (class "Default")
      (node (ref "CONN1") (pin "A25") (pinfunction "ROMCS_A25") (pintype "bidirectional"))
      (node (ref "U$7") (pin "6") (pinfunction "D_6") (pintype "passive"))
    )
    (net (code "101") (name "/ROMCS2") (class "Default")
      (node (ref "CONN1") (pin "B4") (pinfunction "NC3_B4") (pintype "passive"))
      (node (ref "U$7") (pin "3") (pinfunction "D_3") (pintype "passive"))
    )
    (net (code "102") (name "/RTS") (class "Default")
      (node (ref "IC7") (pin "4") (pinfunction "RTS_4") (pintype "output"))
      (node (ref "U$3") (pin "4") (pinfunction "PA5_4") (pintype "passive"))
    )
    (net (code "103") (name "/SDMMC_CK") (class "Default")
      (node (ref "R32") (pin "1") (pinfunction "1_1") (pintype "passive"))
      (node (ref "SD1") (pin "5") (pinfunction "CLK(SCLK)_5") (pintype "input"))
      (node (ref "U1") (pin "13") (pinfunction "IO14_13") (pintype "bidirectional"))
    )
    (net (code "104") (name "/SDMMC_CMD") (class "Default")
      (node (ref "R31") (pin "1") (pinfunction "1_1") (pintype "passive"))
      (node (ref "SD1") (pin "3") (pinfunction "CMD(DI)_3") (pintype "bidirectional"))
      (node (ref "U1") (pin "23") (pinfunction "IO15_23") (pintype "bidirectional"))
    )
    (net (code "105") (name "/SDMMC_D0") (class "Default")
      (node (ref "R33") (pin "2") (pinfunction "2_2") (pintype "passive"))
      (node (ref "SD1") (pin "7") (pinfunction "DAT0(DO)_7") (pintype "bidirectional"))
      (node (ref "U1") (pin "24") (pinfunction "IO2_24") (pintype "bidirectional"))
    )
    (net (code "106") (name "/SDMMC_D1") (class "Default")
      (node (ref "R34") (pin "1") (pinfunction "1_1") (pintype "passive"))
      (node (ref "SD1") (pin "8") (pinfunction "DAT1_8") (pintype "bidirectional"))
      (node (ref "U1") (pin "26") (pinfunction "IO4_26") (pintype "bidirectional"))
    )
    (net (code "107") (name "/SDMMC_D2") (class "Default")
      (node (ref "R29") (pin "2") (pinfunction "2_2") (pintype "passive"))
      (node (ref "SD1") (pin "1") (pinfunction "DAT2_1") (pintype "bidirectional"))
      (node (ref "U1") (pin "14") (pinfunction "IO12_14") (pintype "bidirectional"))
    )
    (net (code "108") (name "/SDMMC_D3") (class "Default")
      (node (ref "R30") (pin "1") (pinfunction "1_1") (pintype "passive"))
      (node (ref "SD1") (pin "2") (pinfunction "CD/DAT3(~{CS})_2") (pintype "bidirectional"))
      (node (ref "U1") (pin "16") (pinfunction "IO13_16") (pintype "bidirectional"))
    )
    (net (code "109") (name "/SDMMC_DET") (class "Default")
      (node (ref "R1") (pin "2") (pinfunction "2_2") (pintype "passive"))
      (node (ref "SD1") (pin "A") (pinfunction "A_A") (pintype "passive"))
      (node (ref "U1") (pin "28") (pinfunction "IO17_28") (pintype "bidirectional"))
    )
    (net (code "110") (name "/SW1") (class "Default")
      (node (ref "C42") (pin "1") (pinfunction "1_1") (pintype "passive"))
      (node (ref "IC5") (pin "3") (pinfunction "SW_3") (pintype "passive"))
      (node (ref "L1") (pin "P$1") (pinfunction "1_P$1") (pintype "passive"))
    )
    (net (code "111") (name "/SW2") (class "Default")
      (node (ref "C43") (pin "1") (pinfunction "1_1") (pintype "passive"))
      (node (ref "IC6") (pin "3") (pinfunction "SW_3") (pintype "passive"))
      (node (ref "L2") (pin "P$1") (pinfunction "1_P$1") (pintype "passive"))
    )
    (net (code "112") (name "/SWITCH") (class "Default")
      (node (ref "R4") (pin "1") (pinfunction "1_1") (pintype "passive"))
      (node (ref "S3") (pin "B2") (pinfunction "2_B2") (pintype "passive"))
      (node (ref "U1") (pin "6") (pinfunction "IO34_6") (pintype "input"))
    )
    (net (code "113") (name "/TCK") (class "Default")
      (node (ref "IC2") (pin "16") (pinfunction "__TCK_16") (pintype "bidirectional"))
      (node (ref "J1") (pin "1") (pinfunction "1_1") (pintype "passive"))
      (node (ref "R10") (pin "1") (pinfunction "1_1") (pintype "passive"))
    )
    (net (code "114") (name "/TDI") (class "Default")
      (node (ref "IC2") (pin "15") (pinfunction "__TDI_15") (pintype "bidirectional"))
      (node (ref "J1") (pin "9") (pinfunction "9_9") (pintype "passive"))
    )
    (net (code "115") (name "/TDO") (class "Default")
      (node (ref "IC2") (pin "20") (pinfunction "__TDO_20") (pintype "bidirectional"))
      (node (ref "J1") (pin "3") (pinfunction "3_3") (pintype "passive"))
      (node (ref "R8") (pin "1") (pinfunction "1_1") (pintype "passive"))
    )
    (net (code "116") (name "/TMS") (class "Default")
      (node (ref "IC2") (pin "18") (pinfunction "__TMS_18") (pintype "bidirectional"))
      (node (ref "J1") (pin "5") (pinfunction "5_5") (pintype "passive"))
      (node (ref "R9") (pin "1") (pinfunction "1_1") (pintype "passive"))
    )
    (net (code "117") (name "/USB_FLT") (class "Default")
      (node (ref "IC1") (pin "3") (pinfunction "FAULT_3") (pintype "output"))
      (node (ref "IC2") (pin "112") (pinfunction "__IO_62_112") (pintype "bidirectional"))
      (node (ref "R38") (pin "1") (pinfunction "1_1") (pintype "passive"))
    )
    (net (code "118") (name "/USB_MODE") (class "Default")
      (node (ref "IC12") (pin "1") (pinfunction "MODE_1") (pintype "input"))
      (node (ref "IC2") (pin "105") (pinfunction "__IO_58_105") (pintype "bidirectional"))
    )
    (net (code "119") (name "/USB_OE") (class "Default")
      (node (ref "IC12") (pin "2") (pinfunction "OE_2") (pintype "input"))
      (node (ref "IC2") (pin "104") (pinfunction "__IO_57_104") (pintype "bidirectional"))
    )
    (net (code "120") (name "/USB_PWREN") (class "Default")
      (node (ref "IC2") (pin "113") (pinfunction "__IO_63_113") (pintype "bidirectional"))
      (node (ref "R37") (pin "2") (pinfunction "2_2") (pintype "passive"))
    )
    (net (code "121") (name "/USB_SPEED") (class "Default")
      (node (ref "IC12") (pin "9") (pinfunction "SPEED_9") (pintype "input"))
      (node (ref "IC2") (pin "106") (pinfunction "__IO_59_106") (pintype "bidirectional"))
    )
    (net (code "122") (name "/USB_SUSPEND") (class "Default")
      (node (ref "IC12") (pin "6") (pinfunction "SUSPND_6") (pintype "input"))
      (node (ref "IC2") (pin "99") (pinfunction "__IO_53_99") (pintype "bidirectional"))
    )
    (net (code "123") (name "/VBUS") (class "Default")
      (node (ref "C59") (pin "+") (pinfunction "+_+") (pintype "passive"))
      (node (ref "IC1") (pin "1") (pinfunction "VOUT_1") (pintype "power_in"))
      (node (ref "TV26") (pin "4") (pinfunction "C_4") (pintype "bidirectional"))
      (node (ref "USB2") (pin "VBUS") (pinfunction "VBUS_VBUS") (pintype "bidirectional"))
    )
    (net (code "124") (name "/VM") (class "Default")
      (node (ref "IC12") (pin "5") (pinfunction "VM_5") (pintype "output"))
      (node (ref "IC2") (pin "100") (pinfunction "__IO_54_100") (pintype "bidirectional"))
    )
    (net (code "125") (name "/VMO") (class "Default")
      (node (ref "IC12") (pin "13") (pinfunction "VMO_13") (pintype "input"))
      (node (ref "IC2") (pin "111") (pinfunction "__IO_61_111") (pintype "bidirectional"))
    )
    (net (code "126") (name "/VP") (class "Default")
      (node (ref "IC12") (pin "4") (pinfunction "VP_4") (pintype "output"))
      (node (ref "IC2") (pin "101") (pinfunction "__IO_55_101") (pintype "bidirectional"))
    )
    (net (code "127") (name "/VPO") (class "Default")
      (node (ref "IC12") (pin "12") (pinfunction "VPO_12") (pintype "input"))
      (node (ref "IC2") (pin "110") (pinfunction "__IO_60_110") (pintype "bidirectional"))
    )
    (net (code "128") (name "/VSENS") (class "Default")
      (node (ref "R46") (pin "1") (pinfunction "1_1") (pintype "passive"))
      (node (ref "U1") (pin "4") (pinfunction "SENSOR_VP_4") (pintype "input"))
    )
    (net (code "129") (name "/WAIT") (class "Default")
      (node (ref "CONN1") (pin "B21") (pinfunction "WAIT_B21") (pintype "bidirectional"))
      (node (ref "IC13") (pin "10") (pinfunction "O_10") (pintype "open_collector"))
    )
    (net (code "130") (name "/WR") (class "Default")
      (node (ref "CONN1") (pin "B19") (pinfunction "WR_B19") (pintype "bidirectional"))
      (node (ref "RN2") (pin "2") (pinfunction "1_2") (pintype "passive"))
    )
    (net (code "131") (name "/XCK") (class "Default")
      (node (ref "IC2") (pin "54") (pinfunction "__IO_27_54") (pintype "bidirectional"))
      (node (ref "IC3") (pin "18") (pinfunction "B1_18") (pintype "bidirectional"))
    )
    (net (code "132") (name "/XD0") (class "Default")
      (node (ref "IC2") (pin "43") (pinfunction "__IO_19_43") (pintype "bidirectional"))
      (node (ref "IC4") (pin "17") (pinfunction "B2_17") (pintype "bidirectional"))
    )
    (net (code "133") (name "/XD1") (class "Default")
      (node (ref "IC2") (pin "44") (pinfunction "__IO_20_44") (pintype "bidirectional"))
      (node (ref "IC4") (pin "16") (pinfunction "B3_16") (pintype "bidirectional"))
    )
    (net (code "134") (name "/XD2") (class "Default")
      (node (ref "IC2") (pin "46") (pinfunction "__IO_21_46") (pintype "bidirectional"))
      (node (ref "IC4") (pin "15") (pinfunction "B4_15") (pintype "bidirectional"))
    )
    (net (code "135") (name "/XD3") (class "Default")
      (node (ref "IC2") (pin "51") (pinfunction "__IO_24_51") (pintype "bidirectional"))
      (node (ref "IC4") (pin "12") (pinfunction "B7_12") (pintype "bidirectional"))
    )
    (net (code "136") (name "/XD4") (class "Default")
      (node (ref "IC2") (pin "52") (pinfunction "__IO_25_52") (pintype "bidirectional"))
      (node (ref "IC4") (pin "11") (pinfunction "B8_11") (pintype "bidirectional"))
    )
    (net (code "137") (name "/XD5") (class "Default")
      (node (ref "IC2") (pin "50") (pinfunction "__IO_23_50") (pintype "bidirectional"))
      (node (ref "IC4") (pin "13") (pinfunction "B6_13") (pintype "bidirectional"))
    )
    (net (code "138") (name "/XD6") (class "Default")
      (node (ref "IC2") (pin "49") (pinfunction "__IO_22_49") (pintype "bidirectional"))
      (node (ref "IC4") (pin "14") (pinfunction "B5_14") (pintype "bidirectional"))
    )
    (net (code "139") (name "/XD7") (class "Default")
      (node (ref "IC2") (pin "42") (pinfunction "__IO_18_42") (pintype "bidirectional"))
      (node (ref "IC4") (pin "18") (pinfunction "B1_18") (pintype "bidirectional"))
    )
    (net (code "140") (name "/XINT") (class "Default")
      (node (ref "IC2") (pin "55") (pinfunction "__IO_28_55") (pintype "bidirectional"))
      (node (ref "IC3") (pin "17") (pinfunction "B2_17") (pintype "bidirectional"))
    )
    (net (code "141") (name "/XIORQ") (class "Default")
      (node (ref "IC2") (pin "59") (pinfunction "__IO_30_59") (pintype "bidirectional"))
      (node (ref "IC3") (pin "15") (pinfunction "B4_15") (pintype "bidirectional"))
    )
    (net (code "142") (name "/XM1") (class "Default")
      (node (ref "IC2") (pin "65") (pinfunction "__IO_33_65") (pintype "bidirectional"))
      (node (ref "IC3") (pin "12") (pinfunction "B7_12") (pintype "bidirectional"))
    )
    (net (code "143") (name "/XMREQ") (class "Default")
      (node (ref "IC2") (pin "58") (pinfunction "__IO_29_58") (pintype "bidirectional"))
      (node (ref "IC3") (pin "16") (pinfunction "B3_16") (pintype "bidirectional"))
    )
    (net (code "144") (name "/XRD") (class "Default")
      (node (ref "IC2") (pin "60") (pinfunction "__IO_31_60") (pintype "bidirectional"))
      (node (ref "IC3") (pin "14") (pinfunction "B5_14") (pintype "bidirectional"))
    )
    (net (code "145") (name "/XRFSH") (class "Default")
      (node (ref "IC2") (pin "66") (pinfunction "__IO_34_66") (pintype "bidirectional"))
      (node (ref "IC3") (pin "11") (pinfunction "B8_11") (pintype "bidirectional"))
    )
    (net (code "146") (name "/XWR") (class "Default")
      (node (ref "IC2") (pin "64") (pinfunction "__IO_32_64") (pintype "bidirectional"))
      (node (ref "IC3") (pin "13") (pinfunction "B6_13") (pintype "bidirectional"))
    )
    (net (code "147") (name "/ZX_A0") (class "Default")
      (node (ref "IC10") (pin "14") (pinfunction "B5_14") (pintype "bidirectional"))
      (node (ref "IC2") (pin "33") (pinfunction "__IO_14_33") (pintype "bidirectional"))
    )
    (net (code "148") (name "/ZX_A1") (class "Default")
      (node (ref "IC10") (pin "13") (pinfunction "B6_13") (pintype "bidirectional"))
      (node (ref "IC2") (pin "34") (pinfunction "__IO_15_34") (pintype "bidirectional"))
    )
    (net (code "149") (name "/ZX_A2") (class "Default")
      (node (ref "IC10") (pin "12") (pinfunction "B7_12") (pintype "bidirectional"))
      (node (ref "IC2") (pin "38") (pinfunction "__IO_16_38") (pintype "bidirectional"))
    )
    (net (code "150") (name "/ZX_A3") (class "Default")
      (node (ref "IC10") (pin "11") (pinfunction "B8_11") (pintype "bidirectional"))
      (node (ref "IC2") (pin "39") (pinfunction "__IO_17_39") (pintype "bidirectional"))
    )
    (net (code "151") (name "/ZX_A4") (class "Default")
      (node (ref "IC11") (pin "15") (pinfunction "B4_15") (pintype "bidirectional"))
      (node (ref "IC2") (pin "71") (pinfunction "__IO_39_71") (pintype "bidirectional"))
    )
    (net (code "152") (name "/ZX_A5") (class "Default")
      (node (ref "IC11") (pin "16") (pinfunction "B3_16") (pintype "bidirectional"))
      (node (ref "IC2") (pin "70") (pinfunction "__IO_38_70") (pintype "bidirectional"))
    )
    (net (code "153") (name "/ZX_A6") (class "Default")
      (node (ref "IC11") (pin "17") (pinfunction "B2_17") (pintype "bidirectional"))
      (node (ref "IC2") (pin "69") (pinfunction "__IO_37_69") (pintype "bidirectional"))
    )
    (net (code "154") (name "/ZX_A7") (class "Default")
      (node (ref "IC11") (pin "18") (pinfunction "B1_18") (pintype "bidirectional"))
      (node (ref "IC2") (pin "68") (pinfunction "__IO_36_68") (pintype "bidirectional"))
    )
    (net (code "155") (name "/ZX_A8") (class "Default")
      (node (ref "IC11") (pin "14") (pinfunction "B5_14") (pintype "bidirectional"))
      (node (ref "IC2") (pin "72") (pinfunction "__IO_40_72") (pintype "bidirectional"))
    )
    (net (code "156") (name "/ZX_A9") (class "Default")
      (node (ref "IC11") (pin "13") (pinfunction "B6_13") (pintype "bidirectional"))
      (node (ref "IC2") (pin "73") (pinfunction "__IO_41_73") (pintype "bidirectional"))
    )
    (net (code "157") (name "/ZX_A10") (class "Default")
      (node (ref "IC11") (pin "12") (pinfunction "B7_12") (pintype "bidirectional"))
      (node (ref "IC2") (pin "74") (pinfunction "__IO_42_74") (pintype "bidirectional"))
    )
    (net (code "158") (name "/ZX_A11") (class "Default")
      (node (ref "IC11") (pin "11") (pinfunction "B8_11") (pintype "bidirectional"))
      (node (ref "IC2") (pin "75") (pinfunction "__IO_43_75") (pintype "bidirectional"))
    )
    (net (code "159") (name "/ZX_A12") (class "Default")
      (node (ref "IC10") (pin "15") (pinfunction "B4_15") (pintype "bidirectional"))
      (node (ref "IC2") (pin "32") (pinfunction "__IO_13_32") (pintype "bidirectional"))
    )
    (net (code "160") (name "/ZX_A13") (class "Default")
      (node (ref "IC10") (pin "16") (pinfunction "B3_16") (pintype "bidirectional"))
      (node (ref "IC2") (pin "31") (pinfunction "__IO_12_31") (pintype "bidirectional"))
    )
    (net (code "161") (name "/ZX_A14") (class "Default")
      (node (ref "IC10") (pin "17") (pinfunction "B2_17") (pintype "bidirectional"))
      (node (ref "IC2") (pin "30") (pinfunction "__IO_11_30") (pintype "bidirectional"))
    )
    (net (code "162") (name "/ZX_A15") (class "Default")
      (node (ref "IC10") (pin "18") (pinfunction "B1_18") (pintype "bidirectional"))
      (node (ref "IC2") (pin "28") (pinfunction "__IO_10_28") (pintype "bidirectional"))
    )
    (net (code "163") (name "GND") (class "Default")
      (node (ref "C1") (pin "1") (pinfunction "1_1") (pintype "passive"))
      (node (ref "C10") (pin "2") (pinfunction "2_2") (pintype "passive"))
      (node (ref "C11") (pin "2") (pinfunction "2_2") (pintype "passive"))
      (node (ref "C12") (pin "2") (pinfunction "2_2") (pintype "passive"))
      (node (ref "C13") (pin "2") (pinfunction "2_2") (pintype "passive"))
      (node (ref "C14") (pin "2") (pinfunction "2_2") (pintype "passive"))
      (node (ref "C15") (pin "2") (pinfunction "2_2") (pintype "passive"))
      (node (ref "C16") (pin "2") (pinfunction "2_2") (pintype "passive"))
      (node (ref "C17") (pin "2") (pinfunction "2_2") (pintype "passive"))
      (node (ref "C18") (pin "2") (pinfunction "2_2") (pintype "passive"))
      (node (ref "C19") (pin "2") (pinfunction "2_2") (pintype "passive"))
      (node (ref "C2") (pin "1") (pinfunction "1_1") (pintype "passive"))
      (node (ref "C20") (pin "2") (pinfunction "2_2") (pintype "passive"))
      (node (ref "C21") (pin "2") (pinfunction "2_2") (pintype "passive"))
      (node (ref "C22") (pin "2") (pinfunction "2_2") (pintype "passive"))
      (node (ref "C23") (pin "2") (pinfunction "2_2") (pintype "passive"))
      (node (ref "C24") (pin "2") (pinfunction "2_2") (pintype "passive"))
      (node (ref "C25") (pin "2") (pinfunction "2_2") (pintype "passive"))
      (node (ref "C26") (pin "2") (pinfunction "2_2") (pintype "passive"))
      (node (ref "C27") (pin "2") (pinfunction "2_2") (pintype "passive"))
      (node (ref "C28") (pin "2") (pinfunction "2_2") (pintype "passive"))
      (node (ref "C29") (pin "2") (pinfunction "2_2") (pintype "passive"))
      (node (ref "C3") (pin "2") (pinfunction "2_2") (pintype "passive"))
      (node (ref "C30") (pin "2") (pinfunction "2_2") (pintype "passive"))
      (node (ref "C31") (pin "1") (pinfunction "1_1") (pintype "passive"))
      (node (ref "C32") (pin "1") (pinfunction "1_1") (pintype "passive"))
      (node (ref "C33") (pin "1") (pinfunction "1_1") (pintype "passive"))
      (node (ref "C34") (pin "1") (pinfunction "1_1") (pintype "passive"))
      (node (ref "C35") (pin "1") (pinfunction "1_1") (pintype "passive"))
      (node (ref "C36") (pin "1") (pinfunction "1_1") (pintype "passive"))
      (node (ref "C37") (pin "2") (pinfunction "2_2") (pintype "passive"))
      (node (ref "C38") (pin "1") (pinfunction "1_1") (pintype "passive"))
      (node (ref "C39") (pin "1") (pinfunction "1_1") (pintype "passive"))
      (node (ref "C4") (pin "2") (pinfunction "2_2") (pintype "passive"))
      (node (ref "C40") (pin "1") (pinfunction "1_1") (pintype "passive"))
      (node (ref "C41") (pin "2") (pinfunction "2_2") (pintype "passive"))
      (node (ref "C45") (pin "1") (pinfunction "1_1") (pintype "passive"))
      (node (ref "C46") (pin "1") (pinfunction "1_1") (pintype "passive"))
      (node (ref "C47") (pin "1") (pinfunction "1_1") (pintype "passive"))
      (node (ref "C48") (pin "1") (pinfunction "1_1") (pintype "passive"))
      (node (ref "C49") (pin "1") (pinfunction "1_1") (pintype "passive"))
      (node (ref "C5") (pin "2") (pinfunction "2_2") (pintype "passive"))
      (node (ref "C50") (pin "2") (pinfunction "2_2") (pintype "passive"))
      (node (ref "C51") (pin "1") (pinfunction "1_1") (pintype "passive"))
      (node (ref "C52") (pin "2") (pinfunction "2_2") (pintype "passive"))
      (node (ref "C53") (pin "2") (pinfunction "2_2") (pintype "passive"))
      (node (ref "C56") (pin "2") (pinfunction "2_2") (pintype "passive"))
      (node (ref "C57") (pin "MINUS") (pinfunction "-_MINUS") (pintype "passive"))
      (node (ref "C58") (pin "1") (pinfunction "1_1") (pintype "passive"))
      (node (ref "C59") (pin "-") (pinfunction "-_-") (pintype "passive"))
      (node (ref "C6") (pin "2") (pinfunction "2_2") (pintype "passive"))
      (node (ref "C60") (pin "MINUS") (pinfunction "-_MINUS") (pintype "passive"))
      (node (ref "C7") (pin "2") (pinfunction "2_2") (pintype "passive"))
      (node (ref "C8") (pin "2") (pinfunction "2_2") (pintype "passive"))
      (node (ref "C9") (pin "2") (pinfunction "2_2") (pintype "passive"))
      (node (ref "CONN1") (pin "A14") (pinfunction "GND_A14") (pintype "power_in"))
      (node (ref "CONN1") (pin "A6") (pinfunction "GND_A6") (pintype "power_in"))
      (node (ref "CONN1") (pin "A7") (pinfunction "GND_A7") (pintype "power_in"))
      (node (ref "IC1") (pin "2") (pinfunction "GND_2") (pintype "power_in"))
      (node (ref "IC10") (pin "10") (pinfunction "GND_10") (pintype "power_in"))
      (node (ref "IC10") (pin "19") (pinfunction "G_19") (pintype "input"))
      (node (ref "IC11") (pin "10") (pinfunction "GND_10") (pintype "power_in"))
      (node (ref "IC11") (pin "19") (pinfunction "G_19") (pintype "input"))
      (node (ref "IC12") (pin "7") (pinfunction "GND_7") (pintype "power_in"))
      (node (ref "IC13") (pin "7") (pinfunction "GND_7") (pintype "power_in"))
      (node (ref "IC2") (pin "108") (pinfunction "__GNDA2_108") (pintype "power_in"))
      (node (ref "IC2") (pin "118") (pinfunction "__GND_12_118") (pintype "power_in"))
      (node (ref "IC2") (pin "123") (pinfunction "__GND_13_123") (pintype "power_in"))
      (node (ref "IC2") (pin "131") (pinfunction "__GND_14_131") (pintype "power_in"))
      (node (ref "IC2") (pin "140") (pinfunction "__GND_15_140") (pintype "power_in"))
      (node (ref "IC2") (pin "145") (pinfunction "TP_145") (pintype "bidirectional"))
      (node (ref "IC2") (pin "19") (pinfunction "__GND_2_19") (pintype "power_in"))
      (node (ref "IC2") (pin "21") (pinfunction "__NCE_21") (pintype "bidirectional"))
      (node (ref "IC2") (pin "22") (pinfunction "__GND_3_22") (pintype "power_in"))
      (node (ref "IC2") (pin "27") (pinfunction "__GND_4_27") (pintype "power_in"))
      (node (ref "IC2") (pin "36") (pinfunction "__GNDA1_36") (pintype "power_in"))
      (node (ref "IC2") (pin "4") (pinfunction "__GND_1_4") (pintype "power_in"))
      (node (ref "IC2") (pin "41") (pinfunction "__GND_5_41") (pintype "power_in"))
      (node (ref "IC2") (pin "48") (pinfunction "__GND_6_48") (pintype "power_in"))
      (node (ref "IC2") (pin "57") (pinfunction "__GND_7_57") (pintype "power_in"))
      (node (ref "IC2") (pin "63") (pinfunction "__GND_8_63") (pintype "power_in"))
      (node (ref "IC2") (pin "79") (pinfunction "__GND_9_79") (pintype "power_in"))
      (node (ref "IC2") (pin "82") (pinfunction "__GND_10_82") (pintype "power_in"))
      (node (ref "IC2") (pin "94") (pinfunction "__MSEL0_94") (pintype "bidirectional"))
      (node (ref "IC2") (pin "95") (pinfunction "__GND_11_95") (pintype "power_in"))
      (node (ref "IC2") (pin "96") (pinfunction "__MSEL1_96") (pintype "bidirectional"))
      (node (ref "IC3") (pin "10") (pinfunction "GND_10") (pintype "power_in"))
      (node (ref "IC3") (pin "19") (pinfunction "G_19") (pintype "input"))
      (node (ref "IC4") (pin "10") (pinfunction "GND_10") (pintype "power_in"))
      (node (ref "IC5") (pin "4") (pinfunction "GND_4") (pintype "power_in"))
      (node (ref "IC6") (pin "4") (pinfunction "GND_4") (pintype "power_in"))
      (node (ref "IC7") (pin "3") (pinfunction "GND_3") (pintype "power_in"))
      (node (ref "IC8") (pin "2") (pinfunction "GND_2") (pintype "power_in"))
      (node (ref "IC9") (pin "4") (pinfunction "GND_4") (pintype "power_in"))
      (node (ref "J1") (pin "10") (pinfunction "10_10") (pintype "passive"))
      (node (ref "J1") (pin "2") (pinfunction "2_2") (pintype "passive"))
      (node (ref "Q1") (pin "2") (pinfunction "S_2") (pintype "passive"))
      (node (ref "R10") (pin "2") (pinfunction "2_2") (pintype "passive"))
      (node (ref "R17") (pin "1") (pinfunction "1_1") (pintype "passive"))
      (node (ref "R18") (pin "1") (pinfunction "1_1") (pintype "passive"))
      (node (ref "R23") (pin "2") (pinfunction "2_2") (pintype "passive"))
      (node (ref "R26") (pin "1") (pinfunction "1_1") (pintype "passive"))
      (node (ref "R43") (pin "1") (pinfunction "1_1") (pintype "passive"))
      (node (ref "R45") (pin "2") (pinfunction "2_2") (pintype "passive"))
      (node (ref "R57") (pin "1") (pinfunction "1_1") (pintype "passive"))
      (node (ref "S1") (pin "A2") (pinfunction "1_A2") (pintype "passive"))
      (node (ref "S2") (pin "A2") (pinfunction "1_A2") (pintype "passive"))
      (node (ref "S3") (pin "A2") (pinfunction "1_A2") (pintype "passive"))
      (node (ref "SD1") (pin "6") (pinfunction "VSS_6") (pintype "power_in"))
      (node (ref "SD1") (pin "B") (pinfunction "B_B") (pintype "passive"))
      (node (ref "SD1") (pin "MNT1") (pinfunction "S1_MNT1") (pintype "passive"))
      (node (ref "SD1") (pin "MNT2") (pinfunction "S2_MNT2") (pintype "passive"))
      (node (ref "SD1") (pin "MNT3") (pinfunction "S3_MNT3") (pintype "passive"))
      (node (ref "SD1") (pin "MNT4") (pinfunction "S4_MNT4") (pintype "passive"))
      (node (ref "TV26") (pin "1") (pinfunction "COM_1") (pintype "bidirectional"))
      (node (ref "U$1") (pin "2") (pinfunction "GND_2") (pintype "power_in"))
      (node (ref "U$3") (pin "2") (pinfunction "GND_2") (pintype "power_in"))
      (node (ref "U$5") (pin "A2") (pinfunction "GND_A2") (pintype "power_in"))
      (node (ref "U$5") (pin "B2") (pinfunction "GND_B2") (pintype "power_in"))
      (node (ref "U1") (pin "1") (pinfunction "GND_1") (pintype "bidirectional"))
      (node (ref "U1") (pin "15") (pinfunction "GND_15") (pintype "bidirectional"))
      (node (ref "U1") (pin "38") (pinfunction "GND_38") (pintype "bidirectional"))
      (node (ref "U1") (pin "GND") (pinfunction "GND_GND") (pintype "bidirectional"))
      (node (ref "USB1") (pin "P5") (pinfunction "GND_P5") (pintype "bidirectional"))
      (node (ref "USB2") (pin "GND") (pinfunction "GND_GND") (pintype "bidirectional"))
    )
    (net (code "164") (name "Net-(C42-Pad2)") (class "Default")
      (node (ref "C42") (pin "2") (pinfunction "2_2") (pintype "passive"))
      (node (ref "R13") (pin "1") (pinfunction "1_1") (pintype "passive"))
    )
    (net (code "165") (name "Net-(C43-Pad2)") (class "Default")
      (node (ref "C43") (pin "2") (pinfunction "2_2") (pintype "passive"))
      (node (ref "R14") (pin "1") (pinfunction "1_1") (pintype "passive"))
    )
    (net (code "166") (name "Net-(C44-Pad1)") (class "Default")
      (node (ref "C44") (pin "1") (pinfunction "1_1") (pintype "passive"))
      (node (ref "R16") (pin "2") (pinfunction "2_2") (pintype "passive"))
      (node (ref "R18") (pin "2") (pinfunction "2_2") (pintype "passive"))
      (node (ref "R20") (pin "1") (pinfunction "1_1") (pintype "passive"))
    )
    (net (code "167") (name "Net-(IC2-__CLK2)") (class "Default")
      (node (ref "IC2") (pin "24") (pinfunction "__CLK2_24") (pintype "input"))
      (node (ref "U$1") (pin "3") (pinfunction "FO_3") (pintype "output"))
    )
    (net (code "168") (name "Net-(IC2-__IO_6{slash}FLASH_NCS{slash}NCSO)") (class "Default")
      (node (ref "IC2") (pin "8") (pinfunction "__IO_6/FLASH_NCS/NCSO_8") (pintype "bidirectional"))
      (node (ref "TP4") (pin "TP") (pinfunction "TP_TP") (pintype "input"))
    )
    (net (code "169") (name "Net-(IC3A-A1)") (class "Default")
      (node (ref "IC3") (pin "2") (pinfunction "A1_2") (pintype "bidirectional"))
      (node (ref "RN1") (pin "8") (pinfunction "2_8") (pintype "passive"))
    )
    (net (code "170") (name "Net-(IC3A-A2)") (class "Default")
      (node (ref "IC3") (pin "3") (pinfunction "A2_3") (pintype "bidirectional"))
      (node (ref "RN1") (pin "7") (pinfunction "2_7") (pintype "passive"))
    )
    (net (code "171") (name "Net-(IC3A-A3)") (class "Default")
      (node (ref "IC3") (pin "4") (pinfunction "A3_4") (pintype "bidirectional"))
      (node (ref "RN1") (pin "6") (pinfunction "2_6") (pintype "passive"))
    )
    (net (code "172") (name "Net-(IC3A-A4)") (class "Default")
      (node (ref "IC3") (pin "5") (pinfunction "A4_5") (pintype "bidirectional"))
      (node (ref "RN1") (pin "5") (pinfunction "2_5") (pintype "passive"))
    )
    (net (code "173") (name "Net-(IC3A-A5)") (class "Default")
      (node (ref "IC3") (pin "6") (pinfunction "A5_6") (pintype "bidirectional"))
      (node (ref "RN2") (pin "8") (pinfunction "2_8") (pintype "passive"))
    )
    (net (code "174") (name "Net-(IC3A-A6)") (class "Default")
      (node (ref "IC3") (pin "7") (pinfunction "A6_7") (pintype "bidirectional"))
      (node (ref "RN2") (pin "7") (pinfunction "2_7") (pintype "passive"))
    )
    (net (code "175") (name "Net-(IC3A-A7)") (class "Default")
      (node (ref "IC3") (pin "8") (pinfunction "A7_8") (pintype "bidirectional"))
      (node (ref "RN2") (pin "6") (pinfunction "2_6") (pintype "passive"))
    )
    (net (code "176") (name "Net-(IC3A-A8)") (class "Default")
      (node (ref "IC3") (pin "9") (pinfunction "A8_9") (pintype "bidirectional"))
      (node (ref "RN2") (pin "5") (pinfunction "2_5") (pintype "passive"))
    )
    (net (code "177") (name "Net-(IC4A-A1)") (class "Default")
      (node (ref "IC4") (pin "2") (pinfunction "A1_2") (pintype "bidirectional"))
      (node (ref "RN7") (pin "8") (pinfunction "2_8") (pintype "passive"))
    )
    (net (code "178") (name "Net-(IC4A-A2)") (class "Default")
      (node (ref "IC4") (pin "3") (pinfunction "A2_3") (pintype "bidirectional"))
      (node (ref "RN7") (pin "7") (pinfunction "2_7") (pintype "passive"))
    )
    (net (code "179") (name "Net-(IC4A-A3)") (class "Default")
      (node (ref "IC4") (pin "4") (pinfunction "A3_4") (pintype "bidirectional"))
      (node (ref "RN7") (pin "6") (pinfunction "2_6") (pintype "passive"))
    )
    (net (code "180") (name "Net-(IC4A-A4)") (class "Default")
      (node (ref "IC4") (pin "5") (pinfunction "A4_5") (pintype "bidirectional"))
      (node (ref "RN7") (pin "5") (pinfunction "2_5") (pintype "passive"))
    )
    (net (code "181") (name "Net-(IC4A-A5)") (class "Default")
      (node (ref "IC4") (pin "6") (pinfunction "A5_6") (pintype "bidirectional"))
      (node (ref "RN8") (pin "8") (pinfunction "2_8") (pintype "passive"))
    )
    (net (code "182") (name "Net-(IC4A-A6)") (class "Default")
      (node (ref "IC4") (pin "7") (pinfunction "A6_7") (pintype "bidirectional"))
      (node (ref "RN8") (pin "7") (pinfunction "2_7") (pintype "passive"))
    )
    (net (code "183") (name "Net-(IC4A-A7)") (class "Default")
      (node (ref "IC4") (pin "8") (pinfunction "A7_8") (pintype "bidirectional"))
      (node (ref "RN8") (pin "6") (pinfunction "2_6") (pintype "passive"))
    )
    (net (code "184") (name "Net-(IC4A-A8)") (class "Default")
      (node (ref "IC4") (pin "9") (pinfunction "A8_9") (pintype "bidirectional"))
      (node (ref "RN8") (pin "5") (pinfunction "2_5") (pintype "passive"))
    )
    (net (code "185") (name "Net-(IC5-BST)") (class "Default")
      (node (ref "IC5") (pin "5") (pinfunction "BST_5") (pintype "passive"))
      (node (ref "R13") (pin "2") (pinfunction "2_2") (pintype "passive"))
    )
    (net (code "186") (name "Net-(IC5-EN)") (class "Default")
      (node (ref "IC5") (pin "6") (pinfunction "EN_6") (pintype "input"))
      (node (ref "R11") (pin "1") (pinfunction "1_1") (pintype "passive"))
    )
    (net (code "187") (name "Net-(IC5-FB)") (class "Default")
      (node (ref "IC5") (pin "8") (pinfunction "FB_8") (pintype "passive"))
      (node (ref "R15") (pin "1") (pinfunction "1_1") (pintype "passive"))
    )
    (net (code "188") (name "Net-(IC5-SS)") (class "Default")
      (node (ref "C38") (pin "2") (pinfunction "2_2") (pintype "passive"))
      (node (ref "IC5") (pin "1") (pinfunction "SS_1") (pintype "passive"))
    )
    (net (code "189") (name "Net-(IC5-VCC)") (class "Default")
      (node (ref "C35") (pin "2") (pinfunction "2_2") (pintype "passive"))
      (node (ref "IC5") (pin "7") (pinfunction "VCC_7") (pintype "passive"))
    )
    (net (code "190") (name "Net-(IC6-BST)") (class "Default")
      (node (ref "IC6") (pin "5") (pinfunction "BST_5") (pintype "passive"))
      (node (ref "R14") (pin "2") (pinfunction "2_2") (pintype "passive"))
    )
    (net (code "191") (name "Net-(IC6-EN)") (class "Default")
      (node (ref "C58") (pin "2") (pinfunction "2_2") (pintype "passive"))
      (node (ref "IC6") (pin "6") (pinfunction "EN_6") (pintype "input"))
      (node (ref "R12") (pin "1") (pinfunction "1_1") (pintype "passive"))
    )
    (net (code "192") (name "Net-(IC6-FB)") (class "Default")
      (node (ref "IC6") (pin "8") (pinfunction "FB_8") (pintype "passive"))
      (node (ref "R16") (pin "1") (pinfunction "1_1") (pintype "passive"))
    )
    (net (code "193") (name "Net-(IC6-SS)") (class "Default")
      (node (ref "C39") (pin "2") (pinfunction "2_2") (pintype "passive"))
      (node (ref "IC6") (pin "1") (pinfunction "SS_1") (pintype "passive"))
    )
    (net (code "194") (name "Net-(IC6-VCC)") (class "Default")
      (node (ref "C36") (pin "2") (pinfunction "2_2") (pintype "passive"))
      (node (ref "IC6") (pin "7") (pinfunction "VCC_7") (pintype "passive"))
    )
    (net (code "195") (name "Net-(IC7-DM)") (class "Default")
      (node (ref "IC7") (pin "2") (pinfunction "DM_2") (pintype "passive"))
      (node (ref "USB1") (pin "P2") (pinfunction "D-_P2") (pintype "bidirectional"))
    )
    (net (code "196") (name "Net-(IC7-DP)") (class "Default")
      (node (ref "IC7") (pin "1") (pinfunction "DP_1") (pintype "passive"))
      (node (ref "USB1") (pin "P3") (pinfunction "D+_P3") (pintype "bidirectional"))
    )
    (net (code "197") (name "Net-(IC10A-A1)") (class "Default")
      (node (ref "IC10") (pin "2") (pinfunction "A1_2") (pintype "bidirectional"))
      (node (ref "RN3") (pin "8") (pinfunction "2_8") (pintype "passive"))
    )
    (net (code "198") (name "Net-(IC10A-A2)") (class "Default")
      (node (ref "IC10") (pin "3") (pinfunction "A2_3") (pintype "bidirectional"))
      (node (ref "RN3") (pin "7") (pinfunction "2_7") (pintype "passive"))
    )
    (net (code "199") (name "Net-(IC10A-A3)") (class "Default")
      (node (ref "IC10") (pin "4") (pinfunction "A3_4") (pintype "bidirectional"))
      (node (ref "RN3") (pin "6") (pinfunction "2_6") (pintype "passive"))
    )
    (net (code "200") (name "Net-(IC10A-A4)") (class "Default")
      (node (ref "IC10") (pin "5") (pinfunction "A4_5") (pintype "bidirectional"))
      (node (ref "RN3") (pin "5") (pinfunction "2_5") (pintype "passive"))
    )
    (net (code "201") (name "Net-(IC10A-A5)") (class "Default")
      (node (ref "IC10") (pin "6") (pinfunction "A5_6") (pintype "bidirectional"))
      (node (ref "RN4") (pin "8") (pinfunction "2_8") (pintype "passive"))
    )
    (net (code "202") (name "Net-(IC10A-A6)") (class "Default")
      (node (ref "IC10") (pin "7") (pinfunction "A6_7") (pintype "bidirectional"))
      (node (ref "RN4") (pin "7") (pinfunction "2_7") (pintype "passive"))
    )
    (net (code "203") (name "Net-(IC10A-A7)") (class "Default")
      (node (ref "IC10") (pin "8") (pinfunction "A7_8") (pintype "bidirectional"))
      (node (ref "RN4") (pin "6") (pinfunction "2_6") (pintype "passive"))
    )
    (net (code "204") (name "Net-(IC10A-A8)") (class "Default")
      (node (ref "IC10") (pin "9") (pinfunction "A8_9") (pintype "bidirectional"))
      (node (ref "RN4") (pin "5") (pinfunction "2_5") (pintype "passive"))
    )
    (net (code "205") (name "Net-(IC11A-A1)") (class "Default")
      (node (ref "IC11") (pin "2") (pinfunction "A1_2") (pintype "bidirectional"))
      (node (ref "RN5") (pin "8") (pinfunction "2_8") (pintype "passive"))
    )
    (net (code "206") (name "Net-(IC11A-A2)") (class "Default")
      (node (ref "IC11") (pin "3") (pinfunction "A2_3") (pintype "bidirectional"))
      (node (ref "RN5") (pin "7") (pinfunction "2_7") (pintype "passive"))
    )
    (net (code "207") (name "Net-(IC11A-A3)") (class "Default")
      (node (ref "IC11") (pin "4") (pinfunction "A3_4") (pintype "bidirectional"))
      (node (ref "RN5") (pin "6") (pinfunction "2_6") (pintype "passive"))
    )
    (net (code "208") (name "Net-(IC11A-A4)") (class "Default")
      (node (ref "IC11") (pin "5") (pinfunction "A4_5") (pintype "bidirectional"))
      (node (ref "RN5") (pin "5") (pinfunction "2_5") (pintype "passive"))
    )
    (net (code "209") (name "Net-(IC11A-A5)") (class "Default")
      (node (ref "IC11") (pin "6") (pinfunction "A5_6") (pintype "bidirectional"))
      (node (ref "RN6") (pin "8") (pinfunction "2_8") (pintype "passive"))
    )
    (net (code "210") (name "Net-(IC11A-A6)") (class "Default")
      (node (ref "IC11") (pin "7") (pinfunction "A6_7") (pintype "bidirectional"))
      (node (ref "RN6") (pin "7") (pinfunction "2_7") (pintype "passive"))
    )
    (net (code "211") (name "Net-(IC11A-A7)") (class "Default")
      (node (ref "IC11") (pin "8") (pinfunction "A7_8") (pintype "bidirectional"))
      (node (ref "RN6") (pin "6") (pinfunction "2_6") (pintype "passive"))
    )
    (net (code "212") (name "Net-(IC11A-A8)") (class "Default")
      (node (ref "IC11") (pin "9") (pinfunction "A8_9") (pintype "bidirectional"))
      (node (ref "RN6") (pin "5") (pinfunction "2_5") (pintype "passive"))
    )
    (net (code "213") (name "Net-(IC12-DM)") (class "Default")
      (node (ref "IC12") (pin "10") (pinfunction "DM_10") (pintype "bidirectional"))
      (node (ref "R36") (pin "1") (pinfunction "1_1") (pintype "passive"))
    )
    (net (code "214") (name "Net-(IC12-DP)") (class "Default")
      (node (ref "IC12") (pin "11") (pinfunction "DP_11") (pintype "bidirectional"))
      (node (ref "R35") (pin "1") (pinfunction "1_1") (pintype "passive"))
    )
    (net (code "215") (name "Net-(IC13C-O)") (class "Default")
      (node (ref "IC13") (pin "6") (pinfunction "O_6") (pintype "open_collector"))
      (node (ref "R25") (pin "2") (pinfunction "2_2") (pintype "passive"))
      (node (ref "U$2") (pin "2") (pinfunction "G_2") (pintype "passive"))
    )
    (net (code "216") (name "Net-(LED1-PadC)") (class "Default")
      (node (ref "LED1") (pin "C") (pinfunction "C_C") (pintype "passive"))
      (node (ref "R21") (pin "1") (pinfunction "1_1") (pintype "passive"))
    )
    (net (code "217") (name "Net-(LED2-PadC)") (class "Default")
      (node (ref "LED2") (pin "C") (pinfunction "C_C") (pintype "passive"))
      (node (ref "R22") (pin "1") (pinfunction "1_1") (pintype "passive"))
    )
    (net (code "218") (name "Net-(LED3-PadC)") (class "Default")
      (node (ref "LED3") (pin "C") (pinfunction "C_C") (pintype "passive"))
      (node (ref "R23") (pin "1") (pinfunction "1_1") (pintype "passive"))
    )
    (net (code "219") (name "Net-(LED4-PadC)") (class "Default")
      (node (ref "LED4") (pin "C") (pinfunction "C_C") (pintype "passive"))
      (node (ref "R39") (pin "1") (pinfunction "1_1") (pintype "passive"))
    )
    (net (code "220") (name "Net-(LED5-PadC)") (class "Default")
      (node (ref "LED5") (pin "C") (pinfunction "C_C") (pintype "passive"))
      (node (ref "R40") (pin "1") (pinfunction "1_1") (pintype "passive"))
    )
    (net (code "221") (name "Net-(LED6-PadC)") (class "Default")
      (node (ref "LED6") (pin "C") (pinfunction "C_C") (pintype "passive"))
      (node (ref "R41") (pin "1") (pinfunction "1_1") (pintype "passive"))
    )
    (net (code "222") (name "Net-(R15-Pad2)") (class "Default")
      (node (ref "R15") (pin "2") (pinfunction "2_2") (pintype "passive"))
      (node (ref "R17") (pin "2") (pinfunction "2_2") (pintype "passive"))
      (node (ref "R19") (pin "1") (pinfunction "1_1") (pintype "passive"))
    )
    (net (code "223") (name "Net-(R26-Pad2)") (class "Default")
      (node (ref "R26") (pin "2") (pinfunction "2_2") (pintype "passive"))
      (node (ref "R44") (pin "1") (pinfunction "1_1") (pintype "passive"))
      (node (ref "R46") (pin "2") (pinfunction "2_2") (pintype "passive"))
    )
    (net (code "224") (name "Net-(U$4A-D)") (class "Default")
      (node (ref "R29") (pin "1") (pinfunction "1_1") (pintype "passive"))
      (node (ref "U$4") (pin "3") (pinfunction "D_3") (pintype "passive"))
    )
    (net (code "225") (name "Net-(U$4B-D)") (class "Default")
      (node (ref "R33") (pin "1") (pinfunction "1_1") (pintype "passive"))
      (node (ref "U$4") (pin "6") (pinfunction "D_6") (pintype "passive"))
    )
    (net (code "226") (name "PE") (class "Default")
      (node (ref "C50") (pin "1") (pinfunction "1_1") (pintype "passive"))
      (node (ref "R45") (pin "1") (pinfunction "1_1") (pintype "passive"))
      (node (ref "USB2") (pin "P$5") (pinfunction "SHIELD_P$5") (pintype "passive"))
      (node (ref "USB2") (pin "P$6") (pinfunction "SHIELD_P$6") (pintype "passive"))
    )
    (net (code "227") (name "unconnected-(CONN1-BUSACK-PadA26)") (class "Default")
      (node (ref "CONN1") (pin "A26") (pinfunction "BUSACK_A26") (pintype "bidirectional"))
    )
    (net (code "228") (name "unconnected-(CONN1-BUSREQ-PadA19)") (class "Default")
      (node (ref "CONN1") (pin "A19") (pinfunction "BUSREQ_A19") (pintype "bidirectional"))
    )
    (net (code "229") (name "unconnected-(CONN1-HALT-PadB15)") (class "Default")
      (node (ref "CONN1") (pin "B15") (pinfunction "HALT_B15") (pintype "bidirectional"))
    )
    (net (code "230") (name "unconnected-(CONN1-NC-PadB28)") (class "Default")
      (node (ref "CONN1") (pin "B28") (pinfunction "NC_B28") (pintype "bidirectional"))
    )
    (net (code "231") (name "unconnected-(CONN1-U-PadA18)") (class "Default")
      (node (ref "CONN1") (pin "A18") (pinfunction "U_A18") (pintype "bidirectional"))
    )
    (net (code "232") (name "unconnected-(CONN1-V-PadA17)") (class "Default")
      (node (ref "CONN1") (pin "A17") (pinfunction "V_A17") (pintype "bidirectional"))
    )
    (net (code "233") (name "unconnected-(CONN1-YL-PadA16)") (class "Default")
      (node (ref "CONN1") (pin "A16") (pinfunction "YL_A16") (pintype "bidirectional"))
    )
    (net (code "234") (name "unconnected-(IC2-__CLK3-Pad25)") (class "Default")
      (node (ref "IC2") (pin "25") (pinfunction "__CLK3_25") (pintype "input"))
    )
    (net (code "235") (name "unconnected-(IC2-__CLK4-Pad91)") (class "Default")
      (node (ref "IC2") (pin "91") (pinfunction "__CLK4_91") (pintype "input"))
    )
    (net (code "236") (name "unconnected-(IC2-__CLK5-Pad90)") (class "Default")
      (node (ref "IC2") (pin "90") (pinfunction "__CLK5_90") (pintype "input"))
    )
    (net (code "237") (name "unconnected-(IC2-__CLK6-Pad89)") (class "Default")
      (node (ref "IC2") (pin "89") (pinfunction "__CLK6_89") (pintype "input"))
    )
    (net (code "238") (name "unconnected-(IC2-__CLK7-Pad88)") (class "Default")
      (node (ref "IC2") (pin "88") (pinfunction "__CLK7_88") (pintype "input"))
    )
    (net (code "239") (name "unconnected-(J1-Pad6)") (class "Default")
      (node (ref "J1") (pin "6") (pinfunction "6_6") (pintype "passive"))
    )
    (net (code "240") (name "unconnected-(J1-Pad7)") (class "Default")
      (node (ref "J1") (pin "7") (pinfunction "7_7") (pintype "passive"))
    )
    (net (code "241") (name "unconnected-(J1-Pad8)") (class "Default")
      (node (ref "J1") (pin "8") (pinfunction "8_8") (pintype "passive"))
    )
    (net (code "242") (name "unconnected-(U1-CLK-Pad20)") (class "Default")
      (node (ref "U1") (pin "20") (pinfunction "CLK_20") (pintype "bidirectional"))
    )
    (net (code "243") (name "unconnected-(U1-CMD-Pad19)") (class "Default")
      (node (ref "U1") (pin "19") (pinfunction "CMD_19") (pintype "bidirectional"))
    )
    (net (code "244") (name "unconnected-(U1-NC-Pad32)") (class "Default")
      (node (ref "U1") (pin "32") (pinfunction "NC_32") (pintype "bidirectional"))
    )
    (net (code "245") (name "unconnected-(U1-SD1-Pad22)") (class "Default")
      (node (ref "U1") (pin "22") (pinfunction "SD1_22") (pintype "bidirectional"))
    )
    (net (code "246") (name "unconnected-(U1-SD2-Pad17)") (class "Default")
      (node (ref "U1") (pin "17") (pinfunction "SD2_17") (pintype "bidirectional"))
    )
    (net (code "247") (name "unconnected-(U1-SD3-Pad18)") (class "Default")
      (node (ref "U1") (pin "18") (pinfunction "SD3_18") (pintype "bidirectional"))
    )
    (net (code "248") (name "unconnected-(U1-SDO-Pad21)") (class "Default")
      (node (ref "U1") (pin "21") (pinfunction "SDO_21") (pintype "bidirectional"))
    )
    (net (code "249") (name "unconnected-(U1-SENSOR_VN-Pad5)") (class "Default")
      (node (ref "U1") (pin "5") (pinfunction "SENSOR_VN_5") (pintype "input"))
    )
    (net (code "250") (name "unconnected-(USB1B-USBID-PadP4)") (class "Default")
      (node (ref "USB1") (pin "P4") (pinfunction "USBID_P4") (pintype "bidirectional"))
    )
    (net (code "251") (name "unconnected-(USB1B-VUSB-PadP1)") (class "Default")
      (node (ref "USB1") (pin "P1") (pinfunction "VUSB_P1") (pintype "bidirectional"))
    )
  )
)
